# 03_-_28PINS_SCHEMATIC.net
KiCad netlist of a schematic drawn in Altium Designer
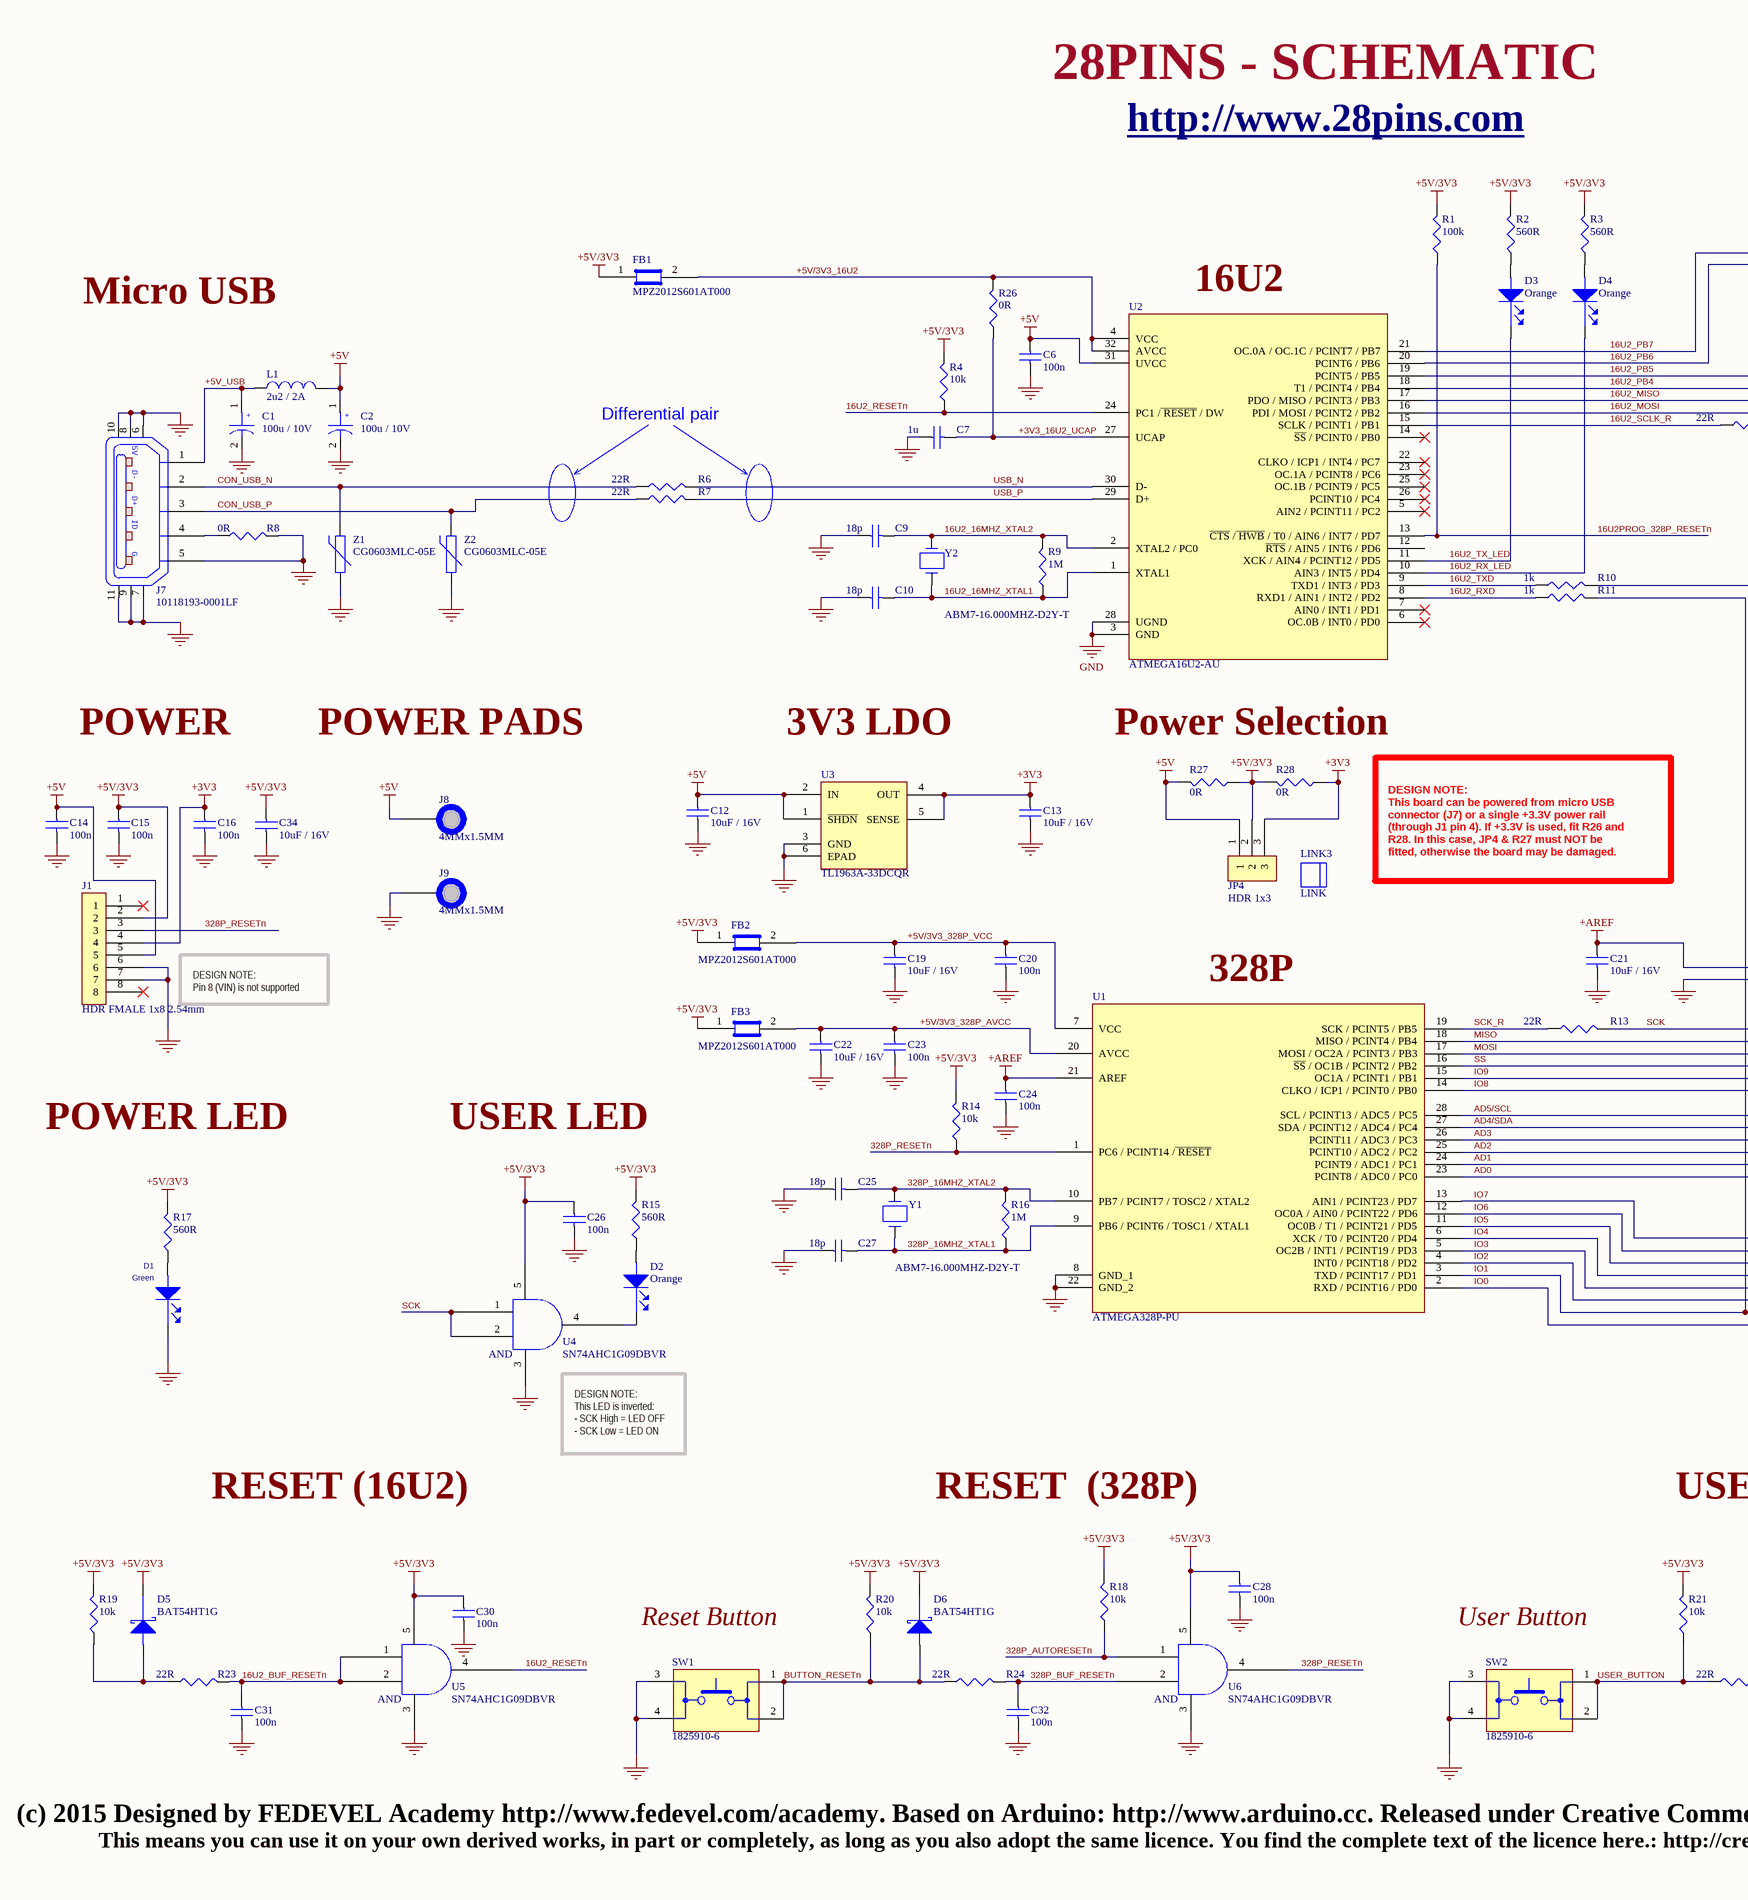
[diagram p0: [03] - 28PINS SCHEMATIC.SchDoc, left]
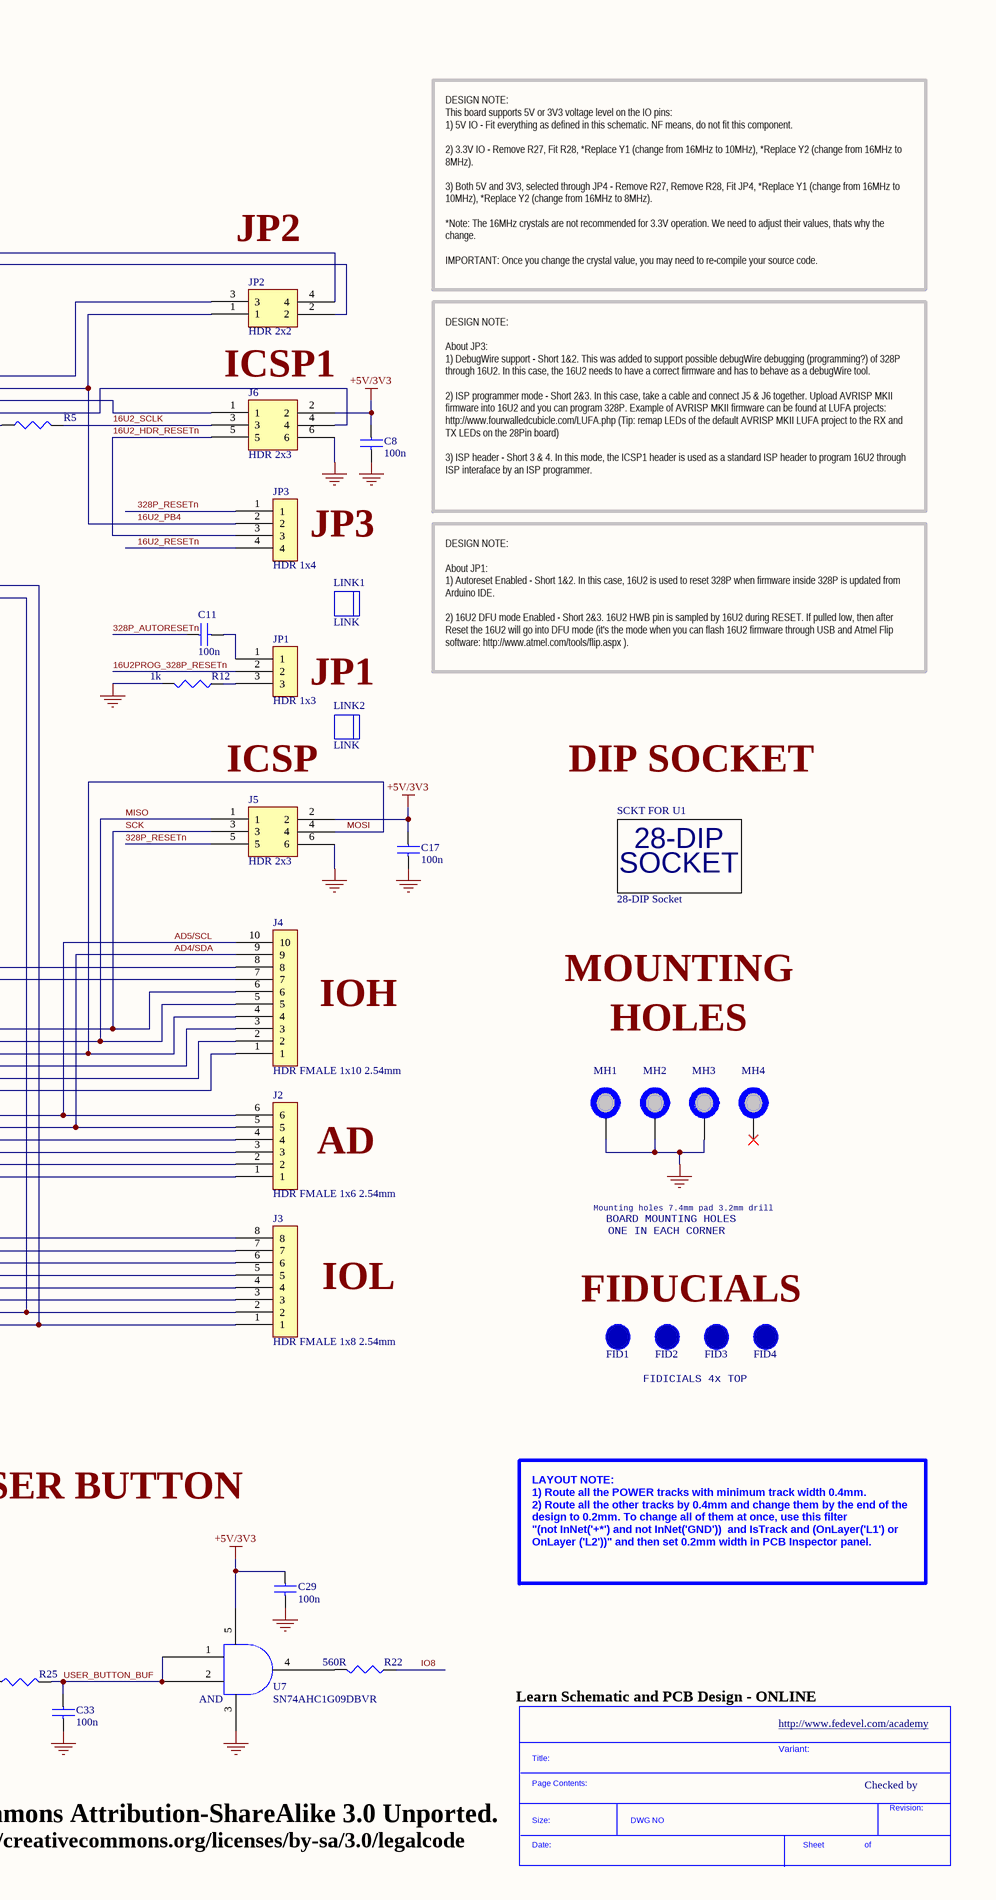
[diagram p1: [03] - 28PINS SCHEMATIC.SchDoc, right]

(export (version "E")
  (design (tool "Eeschema 10.0.6"))
  (components
    (comp (ref "*") (value "SDTitleBlock") (libsource (lib "*") (part "SDTitleBlock")))
    (comp (ref "C1")
      (value "100u / 10V")
      (footprint "C_ALU_C_SIZE")
      (description "CAP ALUM 100UF 10V 20% SMD")
      (fields
        (field (name "MANUFACTURER") "Panasonic Electronic Components")
        (field (name "MANUFACTURER PART NUMBER") "EEE-1AA101WR")
        (field (name ".CREATOR") "MM")
        (field (name ".CHECKED PCB") "RF")
        (field (name ".CHECKED SCH") "RF")
      )
      (libsource (lib "Integrated_Library_FEDEVEL_APR_2015") (part "EEE-1AA101WR"))
    )
    (comp (ref "C2")
      (value "100u / 10V")
      (footprint "C_ALU_C_SIZE")
      (description "CAP ALUM 100UF 10V 20% SMD")
      (fields
        (field (name "MANUFACTURER") "Panasonic Electronic Components")
        (field (name "MANUFACTURER PART NUMBER") "EEE-1AA101WR")
        (field (name ".CREATOR") "MM")
        (field (name ".CHECKED PCB") "RF")
        (field (name ".CHECKED SCH") "RF")
      )
      (libsource (lib "Integrated_Library_FEDEVEL_APR_2015") (part "EEE-1AA101WR"))
    )
    (comp (ref "C6")
      (value "100n")
      (footprint "C0805")
      (description "CAP CER 0.1UF 50V 10% X7R 0805")
      (fields
        (field (name "MANUFACTURER") "TDK Corporation")
        (field (name "MANUFACTURER PART NUMBER") "C2012X7R1H104K085AA")
        (field (name ".CREATOR") "MM")
        (field (name ".CHECKED PCB") "RF")
        (field (name ".CHECKED SCH") "RF")
      )
      (libsource (lib "Integrated_Library_FEDEVEL_APR_2015") (part "C2012X7R1H104K085AA"))
    )
    (comp (ref "C7")
      (value "1u")
      (footprint "C0805")
      (description "CAP CER 1UF 25V 10% X5R 0805")
      (fields
        (field (name "MANUFACTURER") "TDK Corporation")
        (field (name "MANUFACTURER PART NUMBER") "C2012X5R1E105K125AA")
        (field (name ".CREATOR") "MM")
        (field (name ".CHECKED PCB") "RF")
        (field (name ".CHECKED SCH") "RF")
      )
      (libsource (lib "Integrated_Library_FEDEVEL_APR_2015") (part "C2012X5R1E105K125AA"))
    )
    (comp (ref "C8")
      (value "100n")
      (footprint "C0805")
      (description "CAP CER 0.1UF 50V 10% X7R 0805")
      (fields
        (field (name "MANUFACTURER") "TDK Corporation")
        (field (name "MANUFACTURER PART NUMBER") "C2012X7R1H104K085AA")
        (field (name ".CREATOR") "MM")
        (field (name ".CHECKED PCB") "RF")
        (field (name ".CHECKED SCH") "RF")
      )
      (libsource (lib "Integrated_Library_FEDEVEL_APR_2015") (part "C2012X7R1H104K085AA"))
    )
    (comp (ref "C9")
      (value "18p")
      (footprint "C0805")
      (description "CAP CER 18PF 50V 5% NP0 0805")
      (fields
        (field (name "MANUFACTURER") "Kemet")
        (field (name "MANUFACTURER PART NUMBER") "C0805C180J5GACTU")
        (field (name ".CREATOR") "MM")
        (field (name ".CHECKED PCB") "RF")
        (field (name ".CHECKED SCH") "RF")
      )
      (libsource (lib "Integrated_Library_FEDEVEL_APR_2015") (part "C0805C180J5GACTU"))
    )
    (comp (ref "C10")
      (value "18p")
      (footprint "C0805")
      (description "CAP CER 18PF 50V 5% NP0 0805")
      (fields
        (field (name "MANUFACTURER") "Kemet")
        (field (name "MANUFACTURER PART NUMBER") "C0805C180J5GACTU")
        (field (name ".CREATOR") "MM")
        (field (name ".CHECKED PCB") "RF")
        (field (name ".CHECKED SCH") "RF")
      )
      (libsource (lib "Integrated_Library_FEDEVEL_APR_2015") (part "C0805C180J5GACTU"))
    )
    (comp (ref "C11")
      (value "100n")
      (footprint "C0805")
      (description "CAP CER 0.1UF 50V 10% X7R 0805")
      (fields
        (field (name "MANUFACTURER") "TDK Corporation")
        (field (name "MANUFACTURER PART NUMBER") "C2012X7R1H104K085AA")
        (field (name ".CREATOR") "MM")
        (field (name ".CHECKED PCB") "RF")
        (field (name ".CHECKED SCH") "RF")
      )
      (libsource (lib "Integrated_Library_FEDEVEL_APR_2015") (part "C2012X7R1H104K085AA"))
    )
    (comp (ref "C12")
      (value "10uF / 16V")
      (footprint "C0805")
      (description "CAP CER 10UF 16V 20% X5R 0805")
      (fields
        (field (name "MANUFACTURER") "TDK Corporation")
        (field (name "MANUFACTURER PART NUMBER") "C2012X5R1C106M/1.25")
      )
      (libsource (lib "Integrated_Library_FEDEVEL_APR_2015") (part "C2012X5R1C106M"))
    )
    (comp (ref "C13")
      (value "10uF / 16V")
      (footprint "C0805")
      (description "CAP CER 10UF 16V 20% X5R 0805")
      (fields
        (field (name "MANUFACTURER") "TDK Corporation")
        (field (name "MANUFACTURER PART NUMBER") "C2012X5R1C106M/1.25")
      )
      (libsource (lib "Integrated_Library_FEDEVEL_APR_2015") (part "C2012X5R1C106M"))
    )
    (comp (ref "C14")
      (value "100n")
      (footprint "C0805")
      (description "CAP CER 0.1UF 50V 10% X7R 0805")
      (fields
        (field (name "MANUFACTURER") "TDK Corporation")
        (field (name "MANUFACTURER PART NUMBER") "C2012X7R1H104K085AA")
        (field (name ".CREATOR") "MM")
        (field (name ".CHECKED PCB") "RF")
        (field (name ".CHECKED SCH") "RF")
      )
      (libsource (lib "Integrated_Library_FEDEVEL_APR_2015") (part "C2012X7R1H104K085AA"))
    )
    (comp (ref "C15")
      (value "100n")
      (footprint "C0805")
      (description "CAP CER 0.1UF 50V 10% X7R 0805")
      (fields
        (field (name "MANUFACTURER") "TDK Corporation")
        (field (name "MANUFACTURER PART NUMBER") "C2012X7R1H104K085AA")
        (field (name ".CREATOR") "MM")
        (field (name ".CHECKED PCB") "RF")
        (field (name ".CHECKED SCH") "RF")
      )
      (libsource (lib "Integrated_Library_FEDEVEL_APR_2015") (part "C2012X7R1H104K085AA"))
    )
    (comp (ref "C16")
      (value "100n")
      (footprint "C0805")
      (description "CAP CER 0.1UF 50V 10% X7R 0805")
      (fields
        (field (name "MANUFACTURER") "TDK Corporation")
        (field (name "MANUFACTURER PART NUMBER") "C2012X7R1H104K085AA")
        (field (name ".CREATOR") "MM")
        (field (name ".CHECKED PCB") "RF")
        (field (name ".CHECKED SCH") "RF")
      )
      (libsource (lib "Integrated_Library_FEDEVEL_APR_2015") (part "C2012X7R1H104K085AA"))
    )
    (comp (ref "C17")
      (value "100n")
      (footprint "C0805")
      (description "CAP CER 0.1UF 50V 10% X7R 0805")
      (fields
        (field (name "MANUFACTURER") "TDK Corporation")
        (field (name "MANUFACTURER PART NUMBER") "C2012X7R1H104K085AA")
        (field (name ".CREATOR") "MM")
        (field (name ".CHECKED PCB") "RF")
        (field (name ".CHECKED SCH") "RF")
      )
      (libsource (lib "Integrated_Library_FEDEVEL_APR_2015") (part "C2012X7R1H104K085AA"))
    )
    (comp (ref "C19")
      (value "10uF / 16V")
      (footprint "C0805")
      (description "CAP CER 10UF 16V 20% X5R 0805")
      (fields
        (field (name "MANUFACTURER") "TDK Corporation")
        (field (name "MANUFACTURER PART NUMBER") "C2012X5R1C106M/1.25")
      )
      (libsource (lib "Integrated_Library_FEDEVEL_APR_2015") (part "C2012X5R1C106M"))
    )
    (comp (ref "C20")
      (value "100n")
      (footprint "C0805")
      (description "CAP CER 0.1UF 50V 10% X7R 0805")
      (fields
        (field (name "MANUFACTURER") "TDK Corporation")
        (field (name "MANUFACTURER PART NUMBER") "C2012X7R1H104K085AA")
        (field (name ".CREATOR") "MM")
        (field (name ".CHECKED PCB") "RF")
        (field (name ".CHECKED SCH") "RF")
      )
      (libsource (lib "Integrated_Library_FEDEVEL_APR_2015") (part "C2012X7R1H104K085AA"))
    )
    (comp (ref "C21")
      (value "10uF / 16V")
      (footprint "C0805")
      (description "CAP CER 10UF 16V 20% X5R 0805")
      (fields
        (field (name "MANUFACTURER") "TDK Corporation")
        (field (name "MANUFACTURER PART NUMBER") "C2012X5R1C106M/1.25")
      )
      (libsource (lib "Integrated_Library_FEDEVEL_APR_2015") (part "C2012X5R1C106M"))
    )
    (comp (ref "C22")
      (value "10uF / 16V")
      (footprint "C0805")
      (description "CAP CER 10UF 16V 20% X5R 0805")
      (fields
        (field (name "MANUFACTURER") "TDK Corporation")
        (field (name "MANUFACTURER PART NUMBER") "C2012X5R1C106M/1.25")
      )
      (libsource (lib "Integrated_Library_FEDEVEL_APR_2015") (part "C2012X5R1C106M"))
    )
    (comp (ref "C23")
      (value "100n")
      (footprint "C0805")
      (description "CAP CER 0.1UF 50V 10% X7R 0805")
      (fields
        (field (name "MANUFACTURER") "TDK Corporation")
        (field (name "MANUFACTURER PART NUMBER") "C2012X7R1H104K085AA")
        (field (name ".CREATOR") "MM")
        (field (name ".CHECKED PCB") "RF")
        (field (name ".CHECKED SCH") "RF")
      )
      (libsource (lib "Integrated_Library_FEDEVEL_APR_2015") (part "C2012X7R1H104K085AA"))
    )
    (comp (ref "C24")
      (value "100n")
      (footprint "C0805")
      (description "CAP CER 0.1UF 50V 10% X7R 0805")
      (fields
        (field (name "MANUFACTURER") "TDK Corporation")
        (field (name "MANUFACTURER PART NUMBER") "C2012X7R1H104K085AA")
        (field (name ".CREATOR") "MM")
        (field (name ".CHECKED PCB") "RF")
        (field (name ".CHECKED SCH") "RF")
      )
      (libsource (lib "Integrated_Library_FEDEVEL_APR_2015") (part "C2012X7R1H104K085AA"))
    )
    (comp (ref "C25")
      (value "18p")
      (footprint "C0805")
      (description "CAP CER 18PF 50V 5% NP0 0805")
      (fields
        (field (name "MANUFACTURER") "Kemet")
        (field (name "MANUFACTURER PART NUMBER") "C0805C180J5GACTU")
        (field (name ".CREATOR") "MM")
        (field (name ".CHECKED PCB") "RF")
        (field (name ".CHECKED SCH") "RF")
      )
      (libsource (lib "Integrated_Library_FEDEVEL_APR_2015") (part "C0805C180J5GACTU"))
    )
    (comp (ref "C26")
      (value "100n")
      (footprint "C0805")
      (description "CAP CER 0.1UF 50V 10% X7R 0805")
      (fields
        (field (name "MANUFACTURER") "TDK Corporation")
        (field (name "MANUFACTURER PART NUMBER") "C2012X7R1H104K085AA")
        (field (name ".CREATOR") "MM")
        (field (name ".CHECKED PCB") "RF")
        (field (name ".CHECKED SCH") "RF")
      )
      (libsource (lib "Integrated_Library_FEDEVEL_APR_2015") (part "C2012X7R1H104K085AA"))
    )
    (comp (ref "C27")
      (value "18p")
      (footprint "C0805")
      (description "CAP CER 18PF 50V 5% NP0 0805")
      (fields
        (field (name "MANUFACTURER") "Kemet")
        (field (name "MANUFACTURER PART NUMBER") "C0805C180J5GACTU")
        (field (name ".CREATOR") "MM")
        (field (name ".CHECKED PCB") "RF")
        (field (name ".CHECKED SCH") "RF")
      )
      (libsource (lib "Integrated_Library_FEDEVEL_APR_2015") (part "C0805C180J5GACTU"))
    )
    (comp (ref "C28")
      (value "100n")
      (footprint "C0805")
      (description "CAP CER 0.1UF 50V 10% X7R 0805")
      (fields
        (field (name "MANUFACTURER") "TDK Corporation")
        (field (name "MANUFACTURER PART NUMBER") "C2012X7R1H104K085AA")
        (field (name ".CREATOR") "MM")
        (field (name ".CHECKED PCB") "RF")
        (field (name ".CHECKED SCH") "RF")
      )
      (libsource (lib "Integrated_Library_FEDEVEL_APR_2015") (part "C2012X7R1H104K085AA"))
    )
    (comp (ref "C29")
      (value "100n")
      (footprint "C0805")
      (description "CAP CER 0.1UF 50V 10% X7R 0805")
      (fields
        (field (name "MANUFACTURER") "TDK Corporation")
        (field (name "MANUFACTURER PART NUMBER") "C2012X7R1H104K085AA")
        (field (name ".CREATOR") "MM")
        (field (name ".CHECKED PCB") "RF")
        (field (name ".CHECKED SCH") "RF")
      )
      (libsource (lib "Integrated_Library_FEDEVEL_APR_2015") (part "C2012X7R1H104K085AA"))
    )
    (comp (ref "C30")
      (value "100n")
      (footprint "C0805")
      (description "CAP CER 0.1UF 50V 10% X7R 0805")
      (fields
        (field (name "MANUFACTURER") "TDK Corporation")
        (field (name "MANUFACTURER PART NUMBER") "C2012X7R1H104K085AA")
        (field (name ".CREATOR") "MM")
        (field (name ".CHECKED PCB") "RF")
        (field (name ".CHECKED SCH") "RF")
      )
      (libsource (lib "Integrated_Library_FEDEVEL_APR_2015") (part "C2012X7R1H104K085AA"))
    )
    (comp (ref "C31")
      (value "100n")
      (footprint "C0805")
      (description "CAP CER 0.1UF 50V 10% X7R 0805")
      (fields
        (field (name "MANUFACTURER") "TDK Corporation")
        (field (name "MANUFACTURER PART NUMBER") "C2012X7R1H104K085AA")
        (field (name ".CREATOR") "MM")
        (field (name ".CHECKED PCB") "RF")
        (field (name ".CHECKED SCH") "RF")
      )
      (libsource (lib "Integrated_Library_FEDEVEL_APR_2015") (part "C2012X7R1H104K085AA"))
    )
    (comp (ref "C32")
      (value "100n")
      (footprint "C0805")
      (description "CAP CER 0.1UF 50V 10% X7R 0805")
      (fields
        (field (name "MANUFACTURER") "TDK Corporation")
        (field (name "MANUFACTURER PART NUMBER") "C2012X7R1H104K085AA")
        (field (name ".CREATOR") "MM")
        (field (name ".CHECKED PCB") "RF")
        (field (name ".CHECKED SCH") "RF")
      )
      (libsource (lib "Integrated_Library_FEDEVEL_APR_2015") (part "C2012X7R1H104K085AA"))
    )
    (comp (ref "C33")
      (value "100n")
      (footprint "C0805")
      (description "CAP CER 0.1UF 50V 10% X7R 0805")
      (fields
        (field (name "MANUFACTURER") "TDK Corporation")
        (field (name "MANUFACTURER PART NUMBER") "C2012X7R1H104K085AA")
        (field (name ".CREATOR") "MM")
        (field (name ".CHECKED PCB") "RF")
        (field (name ".CHECKED SCH") "RF")
      )
      (libsource (lib "Integrated_Library_FEDEVEL_APR_2015") (part "C2012X7R1H104K085AA"))
    )
    (comp (ref "C34")
      (value "10uF / 16V")
      (footprint "C0805")
      (description "CAP CER 10UF 16V 20% X5R 0805")
      (fields
        (field (name "MANUFACTURER") "TDK Corporation")
        (field (name "MANUFACTURER PART NUMBER") "C2012X5R1C106M/1.25")
      )
      (libsource (lib "Integrated_Library_FEDEVEL_APR_2015") (part "C2012X5R1C106M"))
    )
    (comp (ref "D1")
      (value "Green")
      (footprint "LED_0603")
      (description "LED SMARTLED GREEN 570NM 0603")
      (fields
        (field (name "MANUFACTURER") "OSRAM Opto Semiconductors Inc")
        (field (name "MANUFACTURER PART NUMBER") "LG L29K-G2J1-24-Z")
      )
      (libsource (lib "Integrated_Library_FEDEVEL_APR_2015") (part "LG L29K-G2J1-24-Z"))
    )
    (comp (ref "D2")
      (value "Orange")
      (footprint "LED_0603")
      (description "LED SMARTLED ORANGE 606NM 0603")
      (fields
        (field (name "MANUFACTURER") "OSRAM Opto Semiconductors Inc")
        (field (name "MANUFACTURER PART NUMBER") "LO L29K-H2K1-24-Z")
      )
      (libsource (lib "Integrated_Library_FEDEVEL_APR_2015") (part "LO L29K-H2K1-24-Z"))
    )
    (comp (ref "D3")
      (value "Orange")
      (footprint "LED_0603")
      (description "LED SMARTLED ORANGE 606NM 0603")
      (fields
        (field (name "MANUFACTURER") "OSRAM Opto Semiconductors Inc")
        (field (name "MANUFACTURER PART NUMBER") "LO L29K-H2K1-24-Z")
      )
      (libsource (lib "Integrated_Library_FEDEVEL_APR_2015") (part "LO L29K-H2K1-24-Z"))
    )
    (comp (ref "D4")
      (value "Orange")
      (footprint "LED_0603")
      (description "LED SMARTLED ORANGE 606NM 0603")
      (fields
        (field (name "MANUFACTURER") "OSRAM Opto Semiconductors Inc")
        (field (name "MANUFACTURER PART NUMBER") "LO L29K-H2K1-24-Z")
      )
      (libsource (lib "Integrated_Library_FEDEVEL_APR_2015") (part "LO L29K-H2K1-24-Z"))
    )
    (comp (ref "D5")
      (value "BAT54HT1G")
      (footprint "SOD323")
      (description "DIODE SCHOTTKY 30V 0.2A SOD323")
      (fields (field (name "MANUFACTURER") "Fairchild Semiconductor") (field (name ".CREATOR") "MM"))
      (libsource (lib "Integrated_Library_FEDEVEL_APR_2015") (part "BAT54HT1G"))
    )
    (comp (ref "D6")
      (value "BAT54HT1G")
      (footprint "SOD323")
      (description "DIODE SCHOTTKY 30V 0.2A SOD323")
      (fields (field (name "MANUFACTURER") "Fairchild Semiconductor") (field (name ".CREATOR") "MM"))
      (libsource (lib "Integrated_Library_FEDEVEL_APR_2015") (part "BAT54HT1G"))
    )
    (comp (ref "FB1")
      (value "MPZ2012S601AT000")
      (footprint "C0805")
      (description "FERRITE CHIP BEAD 600 OHM SMD")
      (fields
        (field (name "MANUFACTURER") "TDK Corporation")
        (field (name ".CREATOR") "MM")
        (field (name ".CHECKED PCB") "RF")
        (field (name ".CHECKED SCH") "RF")
      )
      (libsource (lib "Integrated_Library_FEDEVEL_APR_2015") (part "MPZ2012S601AT000"))
    )
    (comp (ref "FB2")
      (value "MPZ2012S601AT000")
      (footprint "C0805")
      (description "FERRITE CHIP BEAD 600 OHM SMD")
      (fields
        (field (name "MANUFACTURER") "TDK Corporation")
        (field (name ".CREATOR") "MM")
        (field (name ".CHECKED PCB") "RF")
        (field (name ".CHECKED SCH") "RF")
      )
      (libsource (lib "Integrated_Library_FEDEVEL_APR_2015") (part "MPZ2012S601AT000"))
    )
    (comp (ref "FB3")
      (value "MPZ2012S601AT000")
      (footprint "C0805")
      (description "FERRITE CHIP BEAD 600 OHM SMD")
      (fields
        (field (name "MANUFACTURER") "TDK Corporation")
        (field (name ".CREATOR") "MM")
        (field (name ".CHECKED PCB") "RF")
        (field (name ".CHECKED SCH") "RF")
      )
      (libsource (lib "Integrated_Library_FEDEVEL_APR_2015") (part "MPZ2012S601AT000"))
    )
    (comp (ref "FID1")
      (value "FID_1MMC")
      (footprint "FID_40X120D")
      (description "Fiducial 40mil Diameter, 120mil Mask")
      (libsource (lib "Integrated_Library_FEDEVEL_APR_2015") (part "FID_1MMC"))
    )
    (comp (ref "FID2")
      (value "FID_1MMC")
      (footprint "FID_40X120D")
      (description "Fiducial 40mil Diameter, 120mil Mask")
      (libsource (lib "Integrated_Library_FEDEVEL_APR_2015") (part "FID_1MMC"))
    )
    (comp (ref "FID3")
      (value "FID_1MMC")
      (footprint "FID_40X120D")
      (description "Fiducial 40mil Diameter, 120mil Mask")
      (libsource (lib "Integrated_Library_FEDEVEL_APR_2015") (part "FID_1MMC"))
    )
    (comp (ref "FID4")
      (value "FID_1MMC")
      (footprint "FID_40X120D")
      (description "Fiducial 40mil Diameter, 120mil Mask")
      (libsource (lib "Integrated_Library_FEDEVEL_APR_2015") (part "FID_1MMC"))
    )
    (comp (ref "J1")
      (value "HDR FMALE 1x8 2.54mm")
      (footprint "Hdr_Female_1x8_2.54mm")
      (description "08-WAY SIL VERT SOCKET L/FREE")
      (fields
        (field (name "MANUFACTURER") "Harwin Inc")
        (field (name "MANUFACTURER PART NUMBER") "M20-7820842")
        (field (name ".CREATOR") "MM")
        (field (name ".CHECKED PCB") "RF")
        (field (name ".CHECKED SCH") "RF")
      )
      (libsource (lib "") (part "M20-7820842_1"))
    )
    (comp (ref "J2")
      (value "HDR FMALE 1x6 2.54mm")
      (footprint "Hdr_Female_1x6_2.54mm")
      (description "06-WAY SIL VERT SOCKET L/FREE")
      (fields
        (field (name "MANUFACTURER") "Harwin Inc")
        (field (name "MANUFACTURER PART NUMBER") "M20-7820646")
        (field (name ".CHECKED PCB") "MM")
        (field (name ".CHECKED SCH") "MM")
        (field (name ".CREATOR") "MM")
      )
      (libsource (lib "Integrated_Library_FEDEVEL_APR_2015") (part "M20-7820646"))
    )
    (comp (ref "J3")
      (value "HDR FMALE 1x8 2.54mm")
      (footprint "Hdr_Female_1x8_2.54mm")
      (description "08-WAY SIL VERT SOCKET L/FREE")
      (fields
        (field (name "MANUFACTURER") "Harwin Inc")
        (field (name "MANUFACTURER PART NUMBER") "M20-7820842")
        (field (name ".CREATOR") "MM")
        (field (name ".CHECKED PCB") "RF")
        (field (name ".CHECKED SCH") "RF")
      )
      (libsource (lib "Integrated_Library_FEDEVEL_APR_2015") (part "M20-7820842"))
    )
    (comp (ref "J4")
      (value "HDR FMALE 1x10 2.54mm")
      (footprint "Hdr_Female_1x10_2.54mm")
      (description "10-WAY SIL VERT SOCKET L/FREE")
      (fields
        (field (name "MANUFACTURER") "Harwin Inc")
        (field (name "MANUFACTURER PART NUMBER") "M20-7821046")
        (field (name ".CREATOR") "MM")
        (field (name ".CHECKED PCB") "RF")
        (field (name ".CHECKED SCH") "RF")
      )
      (libsource (lib "Integrated_Library_FEDEVEL_APR_2015") (part "M20-7821046"))
    )
    (comp (ref "J5")
      (value "HDR 2x3")
      (footprint "HDR_2x3_2.54MM")
      (description "CONN HEADER 6POS .100 STR 30AU")
      (fields
        (field (name "MANUFACTURER") "FCI")
        (field (name "MANUFACTURER PART NUMBER") "67997-106HLF")
        (field (name ".CREATOR") "MM")
        (field (name ".CHECKED PCB") "RF")
        (field (name ".CHECKED SCH") "RF")
      )
      (libsource (lib "Integrated_Library_FEDEVEL_APR_2015") (part "67997-106HLF"))
    )
    (comp (ref "J6")
      (value "HDR 2x3")
      (footprint "HDR_2x3_2.54MM")
      (description "CONN HEADER 6POS .100 STR 30AU")
      (fields
        (field (name "MANUFACTURER") "FCI")
        (field (name "MANUFACTURER PART NUMBER") "67997-106HLF")
        (field (name ".CREATOR") "MM")
        (field (name ".CHECKED PCB") "RF")
        (field (name ".CHECKED SCH") "RF")
      )
      (libsource (lib "Integrated_Library_FEDEVEL_APR_2015") (part "67997-106HLF"))
    )
    (comp (ref "J7")
      (value "10118193-0001LF")
      (footprint "10118193")
      (description "CONN USB MICRO B RECPT SMT R/A")
      (fields
        (field (name "MANUFACTURER") "FCI")
        (field (name ".CREATOR") "MM")
        (field (name ".CHECKED PCB") "RF")
        (field (name ".CHECKED SCH") "MM")
      )
      (libsource (lib "Integrated_Library_FEDEVEL_APR_2015") (part "10118193-0001LF"))
    )
    (comp (ref "J8")
      (value "4MMx1.5MM")
      (footprint "PAD_WITH_HOLE_4MMx1.5MM")
      (description "Pad with a hole 4mm x 1.5mm")
      (libsource (lib "Integrated_Library_FEDEVEL_APR_2015") (part "PAD_WITH_HOLE_4MMx1.5MM"))
    )
    (comp (ref "J9")
      (value "4MMx1.5MM")
      (footprint "PAD_WITH_HOLE_4MMx1.5MM")
      (description "Pad with a hole 4mm x 1.5mm")
      (libsource (lib "Integrated_Library_FEDEVEL_APR_2015") (part "PAD_WITH_HOLE_4MMx1.5MM"))
    )
    (comp (ref "JP1")
      (value "HDR 1x3")
      (footprint "Hdr_1x3_2.54mm")
      (description "BERGSTIK II .100\" SR STRAIGHT")
      (fields
        (field (name "MANUFACTURER") "FCI")
        (field (name "MANUFACTURER PART NUMBER") "68000-103HLF")
        (field (name ".CREATOR") "MM")
      )
      (libsource (lib "Integrated_Library_FEDEVEL_APR_2015") (part "68000-103HLF"))
    )
    (comp (ref "JP2")
      (value "HDR 2x2")
      (footprint "HDR_2x2_2.54MM")
      (description "CONN HEADER 4POS .100 STR 15AU")
      (fields
        (field (name "MANUFACTURER") "FCI")
        (field (name "MANUFACTURER PART NUMBER") "68602-204HLF")
        (field (name ".CREATOR") "MM")
        (field (name ".CHECKED PCB") "RF")
        (field (name ".CHECKED SCH") "RF")
      )
      (libsource (lib "Integrated_Library_FEDEVEL_APR_2015") (part "68602-204HLF"))
    )
    (comp (ref "JP3")
      (value "HDR 1x4")
      (footprint "HDR_1x4_2.54MM")
      (description "CONN HEADER 4POS .100 STR 15AU")
      (fields
        (field (name "MANUFACTURER") "FCI")
        (field (name "MANUFACTURER PART NUMBER") "68001-204HLF")
        (field (name ".CHECKED PCB") "RF")
        (field (name ".CHECKED SCH") "RF")
      )
      (libsource (lib "Integrated_Library_FEDEVEL_APR_2015") (part "68001-204HLF"))
    )
    (comp (ref "JP4")
      (value "HDR 1x3")
      (footprint "Hdr_1x3_2.54mm")
      (description "BERGSTIK II .100\" SR STRAIGHT")
      (fields
        (field (name "MANUFACTURER") "FCI")
        (field (name "MANUFACTURER PART NUMBER") "68000-103HLF")
        (field (name ".CREATOR") "MM")
      )
      (libsource (lib "") (part "68000-103HLF_1"))
    )
    (comp (ref "L1")
      (value "2u2 / 2A")
      (footprint "C1210_IND")
      (description "FIXED IND 2.2UH 2A 80 MOHM SMD")
      (fields
        (field (name "MANUFACTURER") "Kemet")
        (field (name "MANUFACTURER PART NUMBER") "L1210R2R2MDWIT")
        (field (name ".CREATOR") "MM")
        (field (name ".CHECKED PCB") "RF")
        (field (name ".CHECKED SCH") "RF")
      )
      (libsource (lib "Integrated_Library_FEDEVEL_APR_2015") (part "L1210R2R2MDWIT"))
    )
    (comp (ref "LINK1")
      (value "LINK")
      (description "CONN JUMPER SHORTING .100\" GOLD")
      (fields
        (field (name "MANUFACTURER") "Sullins Connector Solutions")
        (field (name "MANUFACTURER PART NUMBER") "QPC02SXGN-RC")
      )
      (libsource (lib "Integrated_Library_FEDEVEL_APR_2015") (part "QPC02SXGN-RC"))
    )
    (comp (ref "LINK2")
      (value "LINK")
      (description "CONN JUMPER SHORTING .100\" GOLD")
      (fields
        (field (name "MANUFACTURER") "Sullins Connector Solutions")
        (field (name "MANUFACTURER PART NUMBER") "QPC02SXGN-RC")
      )
      (libsource (lib "Integrated_Library_FEDEVEL_APR_2015") (part "QPC02SXGN-RC"))
    )
    (comp (ref "LINK3")
      (value "LINK")
      (description "CONN JUMPER SHORTING .100\" GOLD")
      (fields
        (field (name "MANUFACTURER") "Sullins Connector Solutions")
        (field (name "MANUFACTURER PART NUMBER") "QPC02SXGN-RC")
      )
      (libsource (lib "Integrated_Library_FEDEVEL_APR_2015") (part "QPC02SXGN-RC"))
    )
    (comp (ref "MH1")
      (value "MH_7.4MMC_3.2MMD")
      (footprint "MH_7.4MMD_3.2MMD")
      (description "Mounting Hole 7.4mm Diameter, 3.2mm Drill")
      (fields (field (name ".CREATOR") "MM"))
      (libsource (lib "Integrated_Library_FEDEVEL_APR_2015") (part "MH_7.4MMC_3.2MMD"))
    )
    (comp (ref "MH2")
      (value "MH_7.4MMC_3.2MMD")
      (footprint "MH_7.4MMD_3.2MMD")
      (description "Mounting Hole 7.4mm Diameter, 3.2mm Drill")
      (fields (field (name ".CREATOR") "MM"))
      (libsource (lib "Integrated_Library_FEDEVEL_APR_2015") (part "MH_7.4MMC_3.2MMD"))
    )
    (comp (ref "MH3")
      (value "MH_7.4MMC_3.2MMD")
      (footprint "MH_7.4MMD_3.2MMD")
      (description "Mounting Hole 7.4mm Diameter, 3.2mm Drill")
      (fields (field (name ".CREATOR") "MM"))
      (libsource (lib "Integrated_Library_FEDEVEL_APR_2015") (part "MH_7.4MMC_3.2MMD"))
    )
    (comp (ref "MH4")
      (value "MH_7.4MMNC_3.2MMD")
      (footprint "MH_7.4MMD_3.2MMD_NON_COPPER_NPTH")
      (description "Mounting Hole 7.4mm Diameter (Non Copper), 3.2mm Drill NPTH")
      (libsource (lib "Integrated_Library_FEDEVEL_APR_2015") (part "MH_7.4MMNC_3.2MMD"))
    )
    (comp (ref "R1")
      (value "100k")
      (footprint "R0805")
      (description "RES SMD 100K OHM 1% 1/8W 0805")
      (fields
        (field (name "MANUFACTURER") "Yageo")
        (field (name "MANUFACTURER PART NUMBER") "RC0805FR-07100KL")
        (field (name ".CREATOR") "MM")
        (field (name ".CHECKED PCB") "RF")
        (field (name ".CHECKED SCH") "RF")
      )
      (libsource (lib "Integrated_Library_FEDEVEL_APR_2015") (part "RC0805FR-07100KL"))
    )
    (comp (ref "R2")
      (value "560R")
      (footprint "R0805")
      (description "RES SMD 560 OHM 1% 1/8W 0805")
      (fields
        (field (name "MANUFACTURER") "Yageo")
        (field (name "MANUFACTURER PART NUMBER") "RC0805FR-07560RL")
        (field (name ".CREATOR") "MM")
        (field (name ".CHECKED PCB") "RF")
        (field (name ".CHECKED SCH") "RF")
      )
      (libsource (lib "Integrated_Library_FEDEVEL_APR_2015") (part "RC0805FR-07560RL"))
    )
    (comp (ref "R3")
      (value "560R")
      (footprint "R0805")
      (description "RES SMD 560 OHM 1% 1/8W 0805")
      (fields
        (field (name "MANUFACTURER") "Yageo")
        (field (name "MANUFACTURER PART NUMBER") "RC0805FR-07560RL")
        (field (name ".CREATOR") "MM")
        (field (name ".CHECKED PCB") "RF")
        (field (name ".CHECKED SCH") "RF")
      )
      (libsource (lib "Integrated_Library_FEDEVEL_APR_2015") (part "RC0805FR-07560RL"))
    )
    (comp (ref "R4")
      (value "10k")
      (footprint "R0805")
      (description "RES SMD 10K OHM 1% 1/8W 0805")
      (fields
        (field (name "MANUFACTURER") "Yageo")
        (field (name "MANUFACTURER PART NUMBER") "RC0805FR-0710KL")
        (field (name ".CREATOR") "MM")
        (field (name ".CHECKED PCB") "RF")
        (field (name ".CHECKED SCH") "RF")
      )
      (libsource (lib "Integrated_Library_FEDEVEL_APR_2015") (part "RC0805FR-0710KL"))
    )
    (comp (ref "R5")
      (value "22R")
      (footprint "R0805")
      (description "RES SMD 22 OHM 1% 1/8W 0805")
      (fields
        (field (name "MANUFACTURER") "Yageo")
        (field (name "MANUFACTURER PART NUMBER") "RC0805FR-0722RL")
        (field (name ".CREATOR") "MM")
        (field (name ".CHECKED PCB") "RF")
        (field (name ".CHECKED SCH") "RF")
      )
      (libsource (lib "Integrated_Library_FEDEVEL_APR_2015") (part "RC0805FR-0722RL"))
    )
    (comp (ref "R6")
      (value "22R")
      (footprint "R0805")
      (description "RES SMD 22 OHM 1% 1/8W 0805")
      (fields
        (field (name "MANUFACTURER") "Yageo")
        (field (name "MANUFACTURER PART NUMBER") "RC0805FR-0722RL")
        (field (name ".CREATOR") "MM")
        (field (name ".CHECKED PCB") "RF")
        (field (name ".CHECKED SCH") "RF")
      )
      (libsource (lib "Integrated_Library_FEDEVEL_APR_2015") (part "RC0805FR-0722RL"))
    )
    (comp (ref "R7")
      (value "22R")
      (footprint "R0805")
      (description "RES SMD 22 OHM 1% 1/8W 0805")
      (fields
        (field (name "MANUFACTURER") "Yageo")
        (field (name "MANUFACTURER PART NUMBER") "RC0805FR-0722RL")
        (field (name ".CREATOR") "MM")
        (field (name ".CHECKED PCB") "RF")
        (field (name ".CHECKED SCH") "RF")
      )
      (libsource (lib "Integrated_Library_FEDEVEL_APR_2015") (part "RC0805FR-0722RL"))
    )
    (comp (ref "R8")
      (value "0R")
      (footprint "R0805")
      (description "RES 0.0 OHM 1/8W 0805 SMD")
      (fields
        (field (name "MANUFACTURER") "Yageo")
        (field (name "MANUFACTURER PART NUMBER") "RC0805JR-070RL")
        (field (name ".CHECKED PCB") "RF")
        (field (name ".CHECKED SCH") "RF")
      )
      (libsource (lib "Integrated_Library_FEDEVEL_APR_2015") (part "RC0805JR-070RL"))
    )
    (comp (ref "R9")
      (value "1M")
      (footprint "R0805")
      (description "RES SMD 1M OHM 1% 1/8W 0805")
      (fields
        (field (name "MANUFACTURER") "Yageo")
        (field (name "MANUFACTURER PART NUMBER") "RC0805FR-071ML")
        (field (name ".CREATOR") "MM")
        (field (name ".CHECKED PCB") "RF")
        (field (name ".CHECKED SCH") "RF")
      )
      (libsource (lib "Integrated_Library_FEDEVEL_APR_2015") (part "RC0805FR-071ML"))
    )
    (comp (ref "R10")
      (value "1k")
      (footprint "R0805")
      (description "RES SMD 1K OHM 1% 1/8W 0805")
      (fields
        (field (name "MANUFACTURER") "Yageo")
        (field (name "MANUFACTURER PART NUMBER") "RC0805FR-071KL")
        (field (name ".CREATOR") "MM")
        (field (name ".CHECKED PCB") "RF")
        (field (name ".CHECKED SCH") "RF")
      )
      (libsource (lib "Integrated_Library_FEDEVEL_APR_2015") (part "RC0805FR-071KL"))
    )
    (comp (ref "R11")
      (value "1k")
      (footprint "R0805")
      (description "RES SMD 1K OHM 1% 1/8W 0805")
      (fields
        (field (name "MANUFACTURER") "Yageo")
        (field (name "MANUFACTURER PART NUMBER") "RC0805FR-071KL")
        (field (name ".CREATOR") "MM")
        (field (name ".CHECKED PCB") "RF")
        (field (name ".CHECKED SCH") "RF")
      )
      (libsource (lib "Integrated_Library_FEDEVEL_APR_2015") (part "RC0805FR-071KL"))
    )
    (comp (ref "R12")
      (value "1k")
      (footprint "R0805")
      (description "RES SMD 1K OHM 1% 1/8W 0805")
      (fields
        (field (name "MANUFACTURER") "Yageo")
        (field (name "MANUFACTURER PART NUMBER") "RC0805FR-071KL")
        (field (name ".CREATOR") "MM")
        (field (name ".CHECKED PCB") "RF")
        (field (name ".CHECKED SCH") "RF")
      )
      (libsource (lib "Integrated_Library_FEDEVEL_APR_2015") (part "RC0805FR-071KL"))
    )
    (comp (ref "R13")
      (value "22R")
      (footprint "R0805")
      (description "RES SMD 22 OHM 1% 1/8W 0805")
      (fields
        (field (name "MANUFACTURER") "Yageo")
        (field (name "MANUFACTURER PART NUMBER") "RC0805FR-0722RL")
        (field (name ".CREATOR") "MM")
        (field (name ".CHECKED PCB") "RF")
        (field (name ".CHECKED SCH") "RF")
      )
      (libsource (lib "Integrated_Library_FEDEVEL_APR_2015") (part "RC0805FR-0722RL"))
    )
    (comp (ref "R14")
      (value "10k")
      (footprint "R0805")
      (description "RES SMD 10K OHM 1% 1/8W 0805")
      (fields
        (field (name "MANUFACTURER") "Yageo")
        (field (name "MANUFACTURER PART NUMBER") "RC0805FR-0710KL")
        (field (name ".CREATOR") "MM")
        (field (name ".CHECKED PCB") "RF")
        (field (name ".CHECKED SCH") "RF")
      )
      (libsource (lib "Integrated_Library_FEDEVEL_APR_2015") (part "RC0805FR-0710KL"))
    )
    (comp (ref "R15")
      (value "560R")
      (footprint "R0805")
      (description "RES SMD 560 OHM 1% 1/8W 0805")
      (fields
        (field (name "MANUFACTURER") "Yageo")
        (field (name "MANUFACTURER PART NUMBER") "RC0805FR-07560RL")
        (field (name ".CREATOR") "MM")
        (field (name ".CHECKED PCB") "RF")
        (field (name ".CHECKED SCH") "RF")
      )
      (libsource (lib "Integrated_Library_FEDEVEL_APR_2015") (part "RC0805FR-07560RL"))
    )
    (comp (ref "R16")
      (value "1M")
      (footprint "R0805")
      (description "RES SMD 1M OHM 1% 1/8W 0805")
      (fields
        (field (name "MANUFACTURER") "Yageo")
        (field (name "MANUFACTURER PART NUMBER") "RC0805FR-071ML")
        (field (name ".CREATOR") "MM")
        (field (name ".CHECKED PCB") "RF")
        (field (name ".CHECKED SCH") "RF")
      )
      (libsource (lib "Integrated_Library_FEDEVEL_APR_2015") (part "RC0805FR-071ML"))
    )
    (comp (ref "R17")
      (value "560R")
      (footprint "R0805")
      (description "RES SMD 560 OHM 1% 1/8W 0805")
      (fields
        (field (name "MANUFACTURER") "Yageo")
        (field (name "MANUFACTURER PART NUMBER") "RC0805FR-07560RL")
        (field (name ".CREATOR") "MM")
        (field (name ".CHECKED PCB") "RF")
        (field (name ".CHECKED SCH") "RF")
      )
      (libsource (lib "Integrated_Library_FEDEVEL_APR_2015") (part "RC0805FR-07560RL"))
    )
    (comp (ref "R18")
      (value "10k")
      (footprint "R0805")
      (description "RES SMD 10K OHM 1% 1/8W 0805")
      (fields
        (field (name "MANUFACTURER") "Yageo")
        (field (name "MANUFACTURER PART NUMBER") "RC0805FR-0710KL")
        (field (name ".CREATOR") "MM")
        (field (name ".CHECKED PCB") "RF")
        (field (name ".CHECKED SCH") "RF")
      )
      (libsource (lib "Integrated_Library_FEDEVEL_APR_2015") (part "RC0805FR-0710KL"))
    )
    (comp (ref "R19")
      (value "10k")
      (footprint "R0805")
      (description "RES SMD 10K OHM 1% 1/8W 0805")
      (fields
        (field (name "MANUFACTURER") "Yageo")
        (field (name "MANUFACTURER PART NUMBER") "RC0805FR-0710KL")
        (field (name ".CREATOR") "MM")
        (field (name ".CHECKED PCB") "RF")
        (field (name ".CHECKED SCH") "RF")
      )
      (libsource (lib "Integrated_Library_FEDEVEL_APR_2015") (part "RC0805FR-0710KL"))
    )
    (comp (ref "R20")
      (value "10k")
      (footprint "R0805")
      (description "RES SMD 10K OHM 1% 1/8W 0805")
      (fields
        (field (name "MANUFACTURER") "Yageo")
        (field (name "MANUFACTURER PART NUMBER") "RC0805FR-0710KL")
        (field (name ".CREATOR") "MM")
        (field (name ".CHECKED PCB") "RF")
        (field (name ".CHECKED SCH") "RF")
      )
      (libsource (lib "Integrated_Library_FEDEVEL_APR_2015") (part "RC0805FR-0710KL"))
    )
    (comp (ref "R21")
      (value "10k")
      (footprint "R0805")
      (description "RES SMD 10K OHM 1% 1/8W 0805")
      (fields
        (field (name "MANUFACTURER") "Yageo")
        (field (name "MANUFACTURER PART NUMBER") "RC0805FR-0710KL")
        (field (name ".CREATOR") "MM")
        (field (name ".CHECKED PCB") "RF")
        (field (name ".CHECKED SCH") "RF")
      )
      (libsource (lib "Integrated_Library_FEDEVEL_APR_2015") (part "RC0805FR-0710KL"))
    )
    (comp (ref "R22")
      (value "560R")
      (footprint "R0805")
      (description "RES SMD 560 OHM 1% 1/8W 0805")
      (fields
        (field (name "MANUFACTURER") "Yageo")
        (field (name "MANUFACTURER PART NUMBER") "RC0805FR-07560RL")
        (field (name ".CREATOR") "MM")
        (field (name ".CHECKED PCB") "RF")
        (field (name ".CHECKED SCH") "RF")
      )
      (libsource (lib "Integrated_Library_FEDEVEL_APR_2015") (part "RC0805FR-07560RL"))
    )
    (comp (ref "R23")
      (value "22R")
      (footprint "R0805")
      (description "RES SMD 22 OHM 1% 1/8W 0805")
      (fields
        (field (name "MANUFACTURER") "Yageo")
        (field (name "MANUFACTURER PART NUMBER") "RC0805FR-0722RL")
        (field (name ".CREATOR") "MM")
        (field (name ".CHECKED PCB") "RF")
        (field (name ".CHECKED SCH") "RF")
      )
      (libsource (lib "Integrated_Library_FEDEVEL_APR_2015") (part "RC0805FR-0722RL"))
    )
    (comp (ref "R24")
      (value "22R")
      (footprint "R0805")
      (description "RES SMD 22 OHM 1% 1/8W 0805")
      (fields
        (field (name "MANUFACTURER") "Yageo")
        (field (name "MANUFACTURER PART NUMBER") "RC0805FR-0722RL")
        (field (name ".CREATOR") "MM")
        (field (name ".CHECKED PCB") "RF")
        (field (name ".CHECKED SCH") "RF")
      )
      (libsource (lib "Integrated_Library_FEDEVEL_APR_2015") (part "RC0805FR-0722RL"))
    )
    (comp (ref "R25")
      (value "22R")
      (footprint "R0805")
      (description "RES SMD 22 OHM 1% 1/8W 0805")
      (fields
        (field (name "MANUFACTURER") "Yageo")
        (field (name "MANUFACTURER PART NUMBER") "RC0805FR-0722RL")
        (field (name ".CREATOR") "MM")
        (field (name ".CHECKED PCB") "RF")
        (field (name ".CHECKED SCH") "RF")
      )
      (libsource (lib "Integrated_Library_FEDEVEL_APR_2015") (part "RC0805FR-0722RL"))
    )
    (comp (ref "R26")
      (value "0R")
      (footprint "R0805")
      (description "RES 0.0 OHM 1/8W 0805 SMD")
      (fields
        (field (name "MANUFACTURER") "Yageo")
        (field (name "MANUFACTURER PART NUMBER") "RC0805JR-070RL")
        (field (name ".CHECKED PCB") "RF")
        (field (name ".CHECKED SCH") "RF")
      )
      (libsource (lib "Integrated_Library_FEDEVEL_APR_2015") (part "RC0805JR-070RL"))
    )
    (comp (ref "R27")
      (value "0R")
      (footprint "R0805")
      (description "RES 0.0 OHM 1/8W 0805 SMD")
      (fields
        (field (name "MANUFACTURER") "Yageo")
        (field (name "MANUFACTURER PART NUMBER") "RC0805JR-070RL")
        (field (name ".CHECKED PCB") "RF")
        (field (name ".CHECKED SCH") "RF")
      )
      (libsource (lib "Integrated_Library_FEDEVEL_APR_2015") (part "RC0805JR-070RL"))
    )
    (comp (ref "R28")
      (value "0R")
      (footprint "R0805")
      (description "RES 0.0 OHM 1/8W 0805 SMD")
      (fields
        (field (name "MANUFACTURER") "Yageo")
        (field (name "MANUFACTURER PART NUMBER") "RC0805JR-070RL")
        (field (name ".CHECKED PCB") "RF")
        (field (name ".CHECKED SCH") "RF")
      )
      (libsource (lib "Integrated_Library_FEDEVEL_APR_2015") (part "RC0805JR-070RL"))
    )
    (comp (ref "SCKT FOR U1")
      (value "28-DIP Socket")
      (footprint "28_DIP_7.62mm_SOCKET")
      (description "CONN IC DIP SOCKET 28POS TIN")
      (fields
        (field (name "MANUFACTURER") "3M")
        (field (name "MANUFACTURER PART NUMBER") "4828-3004-CP")
        (field (name ".CREATOR") "MM")
        (field (name ".CHECKED PCB") "RF")
        (field (name ".CHECKED SCH") "RF")
      )
      (libsource (lib "Integrated_Library_FEDEVEL_APR_2015") (part "4828-3004-CP"))
    )
    (comp (ref "SW1")
      (value "1825910-6")
      (footprint "1825910-6")
      (description "SWITCH TACTILE SPST-NO 0.05A 24V")
      (fields
        (field (name "MANUFACTURER") "TE Connectivity")
        (field (name ".CREATOR") "MM")
        (field (name ".CHECKED PCB") "RF")
        (field (name ".CHECKED SCH") "RF")
      )
      (libsource (lib "Integrated_Library_FEDEVEL_APR_2015") (part "1825910-6"))
    )
    (comp (ref "SW2")
      (value "1825910-6")
      (footprint "1825910-6")
      (description "SWITCH TACTILE SPST-NO 0.05A 24V")
      (fields
        (field (name "MANUFACTURER") "TE Connectivity")
        (field (name ".CREATOR") "MM")
        (field (name ".CHECKED PCB") "RF")
        (field (name ".CHECKED SCH") "RF")
      )
      (libsource (lib "Integrated_Library_FEDEVEL_APR_2015") (part "1825910-6"))
    )
    (comp (ref "U1")
      (value "ATMEGA328P-PU")
      (footprint "28_DIP_7.62mm")
      (description "IC MCU 8BIT 32KB FLASH 28DIP")
      (fields
        (field (name "MANUFACTURER") "Atmel")
        (field (name ".CREATOR") "MM")
        (field (name ".CHECKED PCB") "RF")
        (field (name ".CHECKED SCH") "RF")
      )
      (libsource (lib "Integrated_Library_FEDEVEL_APR_2015") (part "ATMEGA328P-PU"))
    )
    (comp (ref "U2")
      (value "ATMEGA16U2-AU")
      (footprint "TQFP32")
      (description "IC MCU 8BIT 16KB FLASH 32TQFP")
      (fields
        (field (name "MANUFACTURER") "Atmel")
        (field (name ".CREATOR") "MM")
        (field (name ".CHECKED PCB") "RF")
        (field (name ".CHECKED SCH") "RF")
      )
      (libsource (lib "Integrated_Library_FEDEVEL_APR_2015") (part "ATMEGA16U2-AU"))
    )
    (comp (ref "U3")
      (value "TL1963A-33DCQR")
      (footprint "DCQ (R-PDSO-G6)")
      (description "IC REG LDO 3.3V 1.5A SOT223-6")
      (fields
        (field (name "MANUFACTURER") "Texas Instruments")
        (field (name ".CREATOR") "MM")
        (field (name ".CHECKED PCB") "RF")
        (field (name ".CHECKED SCH") "RF")
      )
      (libsource (lib "Integrated_Library_FEDEVEL_APR_2015") (part "TL1963A-33DCQR"))
    )
    (comp (ref "U4")
      (value "SN74AHC1G09DBVR")
      (footprint "DBV_SOT_23_5")
      (description "IC GATE AND SGL 2INP SOT23-5")
      (fields (field (name "MANUFACTURER") "Texas Instruments") (field (name ".CREATOR") "MM"))
      (libsource (lib "Integrated_Library_FEDEVEL_APR_2015") (part "SN74AHC1G09DBVR"))
    )
    (comp (ref "U5")
      (value "SN74AHC1G09DBVR")
      (footprint "DBV_SOT_23_5")
      (description "IC GATE AND SGL 2INP SOT23-5")
      (fields (field (name "MANUFACTURER") "Texas Instruments") (field (name ".CREATOR") "MM"))
      (libsource (lib "Integrated_Library_FEDEVEL_APR_2015") (part "SN74AHC1G09DBVR"))
    )
    (comp (ref "U6")
      (value "SN74AHC1G09DBVR")
      (footprint "DBV_SOT_23_5")
      (description "IC GATE AND SGL 2INP SOT23-5")
      (fields (field (name "MANUFACTURER") "Texas Instruments") (field (name ".CREATOR") "MM"))
      (libsource (lib "Integrated_Library_FEDEVEL_APR_2015") (part "SN74AHC1G09DBVR"))
    )
    (comp (ref "U7")
      (value "SN74AHC1G09DBVR")
      (footprint "DBV_SOT_23_5")
      (description "IC GATE AND SGL 2INP SOT23-5")
      (fields (field (name "MANUFACTURER") "Texas Instruments") (field (name ".CREATOR") "MM"))
      (libsource (lib "Integrated_Library_FEDEVEL_APR_2015") (part "SN74AHC1G09DBVR"))
    )
    (comp (ref "Y1")
      (value "ABM7-16.000MHZ-D2Y-T")
      (footprint "ABM7_v1_1_BIG")
      (description "CRYSTAL 16MHZ 18PF SMD")
      (fields
        (field (name "MANUFACTURER") "Abracon LLC")
        (field (name ".CREATOR") "MM")
        (field (name ".CHECKED PCB") "RF")
        (field (name ".CHECKED SCH") "RF")
      )
      (libsource (lib "Integrated_Library_FEDEVEL_APR_2015") (part "ABM7-16.000MHZ-D2Y-T"))
    )
    (comp (ref "Y2")
      (value "ABM7-16.000MHZ-D2Y-T")
      (footprint "ABM7_v1_1_BIG")
      (description "CRYSTAL 16MHZ 18PF SMD")
      (fields
        (field (name "MANUFACTURER") "Abracon LLC")
        (field (name ".CREATOR") "MM")
        (field (name ".CHECKED PCB") "RF")
        (field (name ".CHECKED SCH") "RF")
      )
      (libsource (lib "Integrated_Library_FEDEVEL_APR_2015") (part "ABM7-16.000MHZ-D2Y-T"))
    )
    (comp (ref "Z1")
      (value "CG0603MLC-05E")
      (footprint "R0603")
      (description "VARISTOR 0603")
      (fields
        (field (name "MANUFACTURER") "Bourns Inc.")
        (field (name ".CREATOR") "MM")
        (field (name ".CHECKED PCB") "RF")
        (field (name ".CHECKED SCH") "RF")
      )
      (libsource (lib "Integrated_Library_FEDEVEL_APR_2015") (part "CG0603MLC-05E"))
    )
    (comp (ref "Z2")
      (value "CG0603MLC-05E")
      (footprint "R0603")
      (description "VARISTOR 0603")
      (fields
        (field (name "MANUFACTURER") "Bourns Inc.")
        (field (name ".CREATOR") "MM")
        (field (name ".CHECKED PCB") "RF")
        (field (name ".CHECKED SCH") "RF")
      )
      (libsource (lib "Integrated_Library_FEDEVEL_APR_2015") (part "CG0603MLC-05E"))
    )
  )
  (nets
    (net (code "1") (name "+3V3") (class "Default")
      (node (ref "C13") (pin "1") (pinfunction "1_1") (pintype "passive"))
      (node (ref "C16") (pin "1") (pinfunction "1_1") (pintype "passive"))
      (node (ref "J1") (pin "4") (pinfunction "4_4") (pintype "passive"))
      (node (ref "JP4") (pin "3") (pinfunction "3_3") (pintype "passive"))
      (node (ref "R28") (pin "1") (pinfunction "1_1") (pintype "passive"))
      (node (ref "U3") (pin "4") (pinfunction "OUT_4") (pintype "passive"))
      (node (ref "U3") (pin "5") (pinfunction "SENSE_5") (pintype "passive"))
    )
    (net (code "2") (name "+5V") (class "Default")
      (node (ref "C12") (pin "1") (pinfunction "1_1") (pintype "passive"))
      (node (ref "C14") (pin "1") (pinfunction "1_1") (pintype "passive"))
      (node (ref "C2") (pin "1") (pinfunction "1_1") (pintype "passive"))
      (node (ref "C6") (pin "1") (pinfunction "1_1") (pintype "passive"))
      (node (ref "J1") (pin "5") (pinfunction "5_5") (pintype "passive"))
      (node (ref "J8") (pin "1") (pinfunction "1_1") (pintype "passive"))
      (node (ref "JP4") (pin "1") (pinfunction "1_1") (pintype "passive"))
      (node (ref "L1") (pin "2") (pinfunction "2_2") (pintype "passive"))
      (node (ref "R27") (pin "2") (pinfunction "2_2") (pintype "passive"))
      (node (ref "U2") (pin "31") (pinfunction "UVCC_31") (pintype "passive"))
      (node (ref "U3") (pin "1") (pinfunction "~{SHDN}_1") (pintype "passive"))
      (node (ref "U3") (pin "2") (pinfunction "IN_2") (pintype "passive"))
    )
    (net (code "3") (name "+5V{slash}3V3") (class "Default")
      (node (ref "C15") (pin "1") (pinfunction "1_1") (pintype "passive"))
      (node (ref "C17") (pin "1") (pinfunction "1_1") (pintype "passive"))
      (node (ref "C26") (pin "1") (pinfunction "1_1") (pintype "passive"))
      (node (ref "C28") (pin "1") (pinfunction "1_1") (pintype "passive"))
      (node (ref "C29") (pin "1") (pinfunction "1_1") (pintype "passive"))
      (node (ref "C30") (pin "1") (pinfunction "1_1") (pintype "passive"))
      (node (ref "C34") (pin "1") (pinfunction "1_1") (pintype "passive"))
      (node (ref "C8") (pin "1") (pinfunction "1_1") (pintype "passive"))
      (node (ref "D5") (pin "1") (pinfunction "Cathode_1") (pintype "passive"))
      (node (ref "D6") (pin "1") (pinfunction "Cathode_1") (pintype "passive"))
      (node (ref "FB1") (pin "1") (pinfunction "1_1") (pintype "passive"))
      (node (ref "FB2") (pin "1") (pinfunction "1_1") (pintype "passive"))
      (node (ref "FB3") (pin "1") (pinfunction "1_1") (pintype "passive"))
      (node (ref "J1") (pin "2") (pinfunction "2_2") (pintype "passive"))
      (node (ref "J5") (pin "2") (pinfunction "2_2") (pintype "passive"))
      (node (ref "J6") (pin "2") (pinfunction "2_2") (pintype "passive"))
      (node (ref "JP4") (pin "2") (pinfunction "2_2") (pintype "passive"))
      (node (ref "R1") (pin "2") (pinfunction "2_2") (pintype "passive"))
      (node (ref "R14") (pin "2") (pinfunction "2_2") (pintype "passive"))
      (node (ref "R15") (pin "2") (pinfunction "2_2") (pintype "passive"))
      (node (ref "R17") (pin "2") (pinfunction "2_2") (pintype "passive"))
      (node (ref "R18") (pin "2") (pinfunction "2_2") (pintype "passive"))
      (node (ref "R19") (pin "2") (pinfunction "2_2") (pintype "passive"))
      (node (ref "R2") (pin "2") (pinfunction "2_2") (pintype "passive"))
      (node (ref "R20") (pin "2") (pinfunction "2_2") (pintype "passive"))
      (node (ref "R21") (pin "2") (pinfunction "2_2") (pintype "passive"))
      (node (ref "R27") (pin "1") (pinfunction "1_1") (pintype "passive"))
      (node (ref "R28") (pin "2") (pinfunction "2_2") (pintype "passive"))
      (node (ref "R3") (pin "2") (pinfunction "2_2") (pintype "passive"))
      (node (ref "R4") (pin "2") (pinfunction "2_2") (pintype "passive"))
      (node (ref "U4") (pin "5") (pinfunction "VCC_5") (pintype "power_in"))
      (node (ref "U5") (pin "5") (pinfunction "VCC_5") (pintype "power_in"))
      (node (ref "U6") (pin "5") (pinfunction "VCC_5") (pintype "power_in"))
      (node (ref "U7") (pin "5") (pinfunction "VCC_5") (pintype "power_in"))
    )
    (net (code "4") (name "+AREF") (class "Default")
      (node (ref "C21") (pin "1") (pinfunction "1_1") (pintype "passive"))
      (node (ref "C24") (pin "1") (pinfunction "1_1") (pintype "passive"))
      (node (ref "J4") (pin "8") (pinfunction "8_8") (pintype "passive"))
      (node (ref "U1") (pin "21") (pinfunction "AREF_21") (pintype "passive"))
    )
    (net (code "5") (name "/+3V3_16U2_UCAP") (class "Default")
      (node (ref "C7") (pin "2") (pinfunction "2_2") (pintype "passive"))
      (node (ref "R26") (pin "1") (pinfunction "1_1") (pintype "passive"))
      (node (ref "U2") (pin "27") (pinfunction "UCAP_27") (pintype "passive"))
    )
    (net (code "6") (name "/+5V_USB") (class "Default")
      (node (ref "C1") (pin "1") (pinfunction "1_1") (pintype "passive"))
      (node (ref "J7") (pin "1") (pinfunction "P1_1") (pintype "passive"))
      (node (ref "L1") (pin "1") (pinfunction "1_1") (pintype "passive"))
    )
    (net (code "7") (name "/+5V{slash}3V3_16U2") (class "Default")
      (node (ref "FB1") (pin "2") (pinfunction "2_2") (pintype "passive"))
      (node (ref "R26") (pin "2") (pinfunction "2_2") (pintype "passive"))
      (node (ref "U2") (pin "32") (pinfunction "AVCC_32") (pintype "passive"))
      (node (ref "U2") (pin "4") (pinfunction "VCC_4") (pintype "passive"))
    )
    (net (code "8") (name "/+5V{slash}3V3_328P_AVCC") (class "Default")
      (node (ref "C22") (pin "1") (pinfunction "1_1") (pintype "passive"))
      (node (ref "C23") (pin "1") (pinfunction "1_1") (pintype "passive"))
      (node (ref "FB3") (pin "2") (pinfunction "2_2") (pintype "passive"))
      (node (ref "U1") (pin "20") (pinfunction "AVCC_20") (pintype "passive"))
    )
    (net (code "9") (name "/+5V{slash}3V3_328P_VCC") (class "Default")
      (node (ref "C19") (pin "1") (pinfunction "1_1") (pintype "passive"))
      (node (ref "C20") (pin "1") (pinfunction "1_1") (pintype "passive"))
      (node (ref "FB2") (pin "2") (pinfunction "2_2") (pintype "passive"))
      (node (ref "U1") (pin "7") (pinfunction "VCC_7") (pintype "passive"))
    )
    (net (code "10") (name "/16U2PROG_328P_RESETn") (class "Default")
      (node (ref "JP1") (pin "2") (pinfunction "2_2") (pintype "passive"))
      (node (ref "R1") (pin "1") (pinfunction "1_1") (pintype "passive"))
      (node (ref "U2") (pin "13") (pinfunction "~{CTS}_/~{_HWB}_/_T0_/_AIN6_/_INT7_/_PD7_13") (pintype "passive"))
    )
    (net (code "11") (name "/16U2_16MHZ_XTAL1") (class "Default")
      (node (ref "C10") (pin "2") (pinfunction "2_2") (pintype "passive"))
      (node (ref "R9") (pin "1") (pinfunction "1_1") (pintype "passive"))
      (node (ref "U2") (pin "1") (pinfunction "XTAL1_1") (pintype "passive"))
      (node (ref "Y2") (pin "1") (pinfunction "1_1") (pintype "passive"))
    )
    (net (code "12") (name "/16U2_16MHZ_XTAL2") (class "Default")
      (node (ref "C9") (pin "2") (pinfunction "2_2") (pintype "passive"))
      (node (ref "R9") (pin "2") (pinfunction "2_2") (pintype "passive"))
      (node (ref "U2") (pin "2") (pinfunction "XTAL2_/_PC0_2") (pintype "passive"))
      (node (ref "Y2") (pin "2") (pinfunction "2_2") (pintype "passive"))
    )
    (net (code "13") (name "/16U2_BUF_RESETn") (class "Default")
      (node (ref "C31") (pin "1") (pinfunction "1_1") (pintype "passive"))
      (node (ref "R23") (pin "2") (pinfunction "2_2") (pintype "passive"))
      (node (ref "U5") (pin "1") (pinfunction "A_1") (pintype "passive"))
      (node (ref "U5") (pin "2") (pinfunction "B_2") (pintype "passive"))
    )
    (net (code "14") (name "/16U2_HDR_RESETn") (class "Default")
      (node (ref "J6") (pin "5") (pinfunction "5_5") (pintype "passive"))
      (node (ref "JP3") (pin "3") (pinfunction "3_3") (pintype "passive"))
    )
    (net (code "15") (name "/16U2_MISO") (class "Default")
      (node (ref "J6") (pin "1") (pinfunction "1_1") (pintype "passive"))
      (node (ref "U2") (pin "17") (pinfunction "PDO_/_MISO_/_PCINT3_/_PB3_17") (pintype "passive"))
    )
    (net (code "16") (name "/16U2_MOSI") (class "Default")
      (node (ref "J6") (pin "4") (pinfunction "4_4") (pintype "passive"))
      (node (ref "U2") (pin "16") (pinfunction "PDI_/_MOSI_/_PCINT2_/_PB2_16") (pintype "passive"))
    )
    (net (code "17") (name "/16U2_PB4") (class "Default")
      (node (ref "JP2") (pin "1") (pinfunction "1_1") (pintype "passive"))
      (node (ref "JP3") (pin "2") (pinfunction "2_2") (pintype "passive"))
      (node (ref "U2") (pin "18") (pinfunction "T1_/_PCINT4_/_PB4_18") (pintype "passive"))
    )
    (net (code "18") (name "/16U2_PB5") (class "Default")
      (node (ref "JP2") (pin "3") (pinfunction "3_3") (pintype "passive"))
      (node (ref "U2") (pin "19") (pinfunction "PCINT5_/_PB5_19") (pintype "passive"))
    )
    (net (code "19") (name "/16U2_PB6") (class "Default")
      (node (ref "JP2") (pin "2") (pinfunction "2_2") (pintype "passive"))
      (node (ref "U2") (pin "20") (pinfunction "PCINT6_/_PB6_20") (pintype "passive"))
    )
    (net (code "20") (name "/16U2_PB7") (class "Default")
      (node (ref "JP2") (pin "4") (pinfunction "4_4") (pintype "passive"))
      (node (ref "U2") (pin "21") (pinfunction "OC.0A_/_OC.1C_/_PCINT7_/_PB7_21") (pintype "passive"))
    )
    (net (code "21") (name "/16U2_RESETn") (class "Default")
      (node (ref "JP3") (pin "4") (pinfunction "4_4") (pintype "passive"))
      (node (ref "R4") (pin "1") (pinfunction "1_1") (pintype "passive"))
      (node (ref "U2") (pin "24") (pinfunction "PC1_/~{_RESET}_/_DW_24") (pintype "passive"))
      (node (ref "U5") (pin "4") (pinfunction "Y_4") (pintype "passive"))
    )
    (net (code "22") (name "/16U2_RXD") (class "Default")
      (node (ref "R11") (pin "1") (pinfunction "1_1") (pintype "passive"))
      (node (ref "U2") (pin "8") (pinfunction "RXD1_/_AIN1_/_INT2_/_PD2_8") (pintype "passive"))
    )
    (net (code "23") (name "/16U2_RX_LED") (class "Default")
      (node (ref "D4") (pin "1") (pinfunction "cathode_1") (pintype "passive"))
      (node (ref "U2") (pin "10") (pinfunction "AIN3_/_INT5_/_PD4_10") (pintype "passive"))
    )
    (net (code "24") (name "/16U2_SCLK") (class "Default")
      (node (ref "J6") (pin "3") (pinfunction "3_3") (pintype "passive"))
      (node (ref "R5") (pin "2") (pinfunction "2_2") (pintype "passive"))
    )
    (net (code "25") (name "/16U2_SCLK_R") (class "Default")
      (node (ref "R5") (pin "1") (pinfunction "1_1") (pintype "passive"))
      (node (ref "U2") (pin "15") (pinfunction "SCLK_/_PCINT1_/_PB1_15") (pintype "passive"))
    )
    (net (code "26") (name "/16U2_TXD") (class "Default")
      (node (ref "R10") (pin "1") (pinfunction "1_1") (pintype "passive"))
      (node (ref "U2") (pin "9") (pinfunction "TXD1_/_INT3_/_PD3_9") (pintype "passive"))
    )
    (net (code "27") (name "/16U2_TX_LED") (class "Default")
      (node (ref "D3") (pin "1") (pinfunction "cathode_1") (pintype "passive"))
      (node (ref "U2") (pin "11") (pinfunction "XCK_/_AIN4_/_PCINT12_/_PD5_11") (pintype "passive"))
    )
    (net (code "28") (name "/328P_16MHZ_XTAL1") (class "Default")
      (node (ref "C27") (pin "2") (pinfunction "2_2") (pintype "passive"))
      (node (ref "R16") (pin "1") (pinfunction "1_1") (pintype "passive"))
      (node (ref "U1") (pin "9") (pinfunction "PB6_/_PCINT6_/_TOSC1_/_XTAL1_9") (pintype "passive"))
      (node (ref "Y1") (pin "1") (pinfunction "1_1") (pintype "passive"))
    )
    (net (code "29") (name "/328P_16MHZ_XTAL2") (class "Default")
      (node (ref "C25") (pin "2") (pinfunction "2_2") (pintype "passive"))
      (node (ref "R16") (pin "2") (pinfunction "2_2") (pintype "passive"))
      (node (ref "U1") (pin "10") (pinfunction "PB7_/_PCINT7_/_TOSC2_/_XTAL2_10") (pintype "passive"))
      (node (ref "Y1") (pin "2") (pinfunction "2_2") (pintype "passive"))
    )
    (net (code "30") (name "/328P_AUTORESETn") (class "Default")
      (node (ref "C11") (pin "1") (pinfunction "1_1") (pintype "passive"))
      (node (ref "R18") (pin "1") (pinfunction "1_1") (pintype "passive"))
      (node (ref "U6") (pin "1") (pinfunction "A_1") (pintype "passive"))
    )
    (net (code "31") (name "/328P_BUF_RESETn") (class "Default")
      (node (ref "C32") (pin "1") (pinfunction "1_1") (pintype "passive"))
      (node (ref "R24") (pin "2") (pinfunction "2_2") (pintype "passive"))
      (node (ref "U6") (pin "2") (pinfunction "B_2") (pintype "passive"))
    )
    (net (code "32") (name "/328P_RESETn") (class "Default")
      (node (ref "J1") (pin "3") (pinfunction "3_3") (pintype "passive"))
      (node (ref "J5") (pin "5") (pinfunction "5_5") (pintype "passive"))
      (node (ref "JP3") (pin "1") (pinfunction "1_1") (pintype "passive"))
      (node (ref "R14") (pin "1") (pinfunction "1_1") (pintype "passive"))
      (node (ref "U1") (pin "1") (pinfunction "PC6_/_PCINT14_/~{_RESET}_1") (pintype "passive"))
      (node (ref "U6") (pin "4") (pinfunction "Y_4") (pintype "passive"))
    )
    (net (code "33") (name "/AD0") (class "Default")
      (node (ref "J2") (pin "1") (pinfunction "1_1") (pintype "passive"))
      (node (ref "U1") (pin "23") (pinfunction "PCINT8_/_ADC0_/_PC0_23") (pintype "passive"))
    )
    (net (code "34") (name "/AD1") (class "Default")
      (node (ref "J2") (pin "2") (pinfunction "2_2") (pintype "passive"))
      (node (ref "U1") (pin "24") (pinfunction "PCINT9_/_ADC1_/_PC1_24") (pintype "passive"))
    )
    (net (code "35") (name "/AD2") (class "Default")
      (node (ref "J2") (pin "3") (pinfunction "3_3") (pintype "passive"))
      (node (ref "U1") (pin "25") (pinfunction "PCINT10_/_ADC2_/_PC2_25") (pintype "passive"))
    )
    (net (code "36") (name "/AD3") (class "Default")
      (node (ref "J2") (pin "4") (pinfunction "4_4") (pintype "passive"))
      (node (ref "U1") (pin "26") (pinfunction "PCINT11_/_ADC3_/_PC3_26") (pintype "passive"))
    )
    (net (code "37") (name "/AD4{slash}SDA") (class "Default")
      (node (ref "J2") (pin "5") (pinfunction "5_5") (pintype "passive"))
      (node (ref "J4") (pin "9") (pinfunction "9_9") (pintype "passive"))
      (node (ref "U1") (pin "27") (pinfunction "SDA_/_PCINT12_/_ADC4_/_PC4_27") (pintype "passive"))
    )
    (net (code "38") (name "/AD5{slash}SCL") (class "Default")
      (node (ref "J2") (pin "6") (pinfunction "6_6") (pintype "passive"))
      (node (ref "J4") (pin "10") (pinfunction "10_10") (pintype "passive"))
      (node (ref "U1") (pin "28") (pinfunction "SCL_/_PCINT13_/_ADC5_/_PC5_28") (pintype "passive"))
    )
    (net (code "39") (name "/BUTTON_RESETn") (class "Default")
      (node (ref "D6") (pin "2") (pinfunction "Anode_2") (pintype "passive"))
      (node (ref "R20") (pin "1") (pinfunction "1_1") (pintype "passive"))
      (node (ref "R24") (pin "1") (pinfunction "1_1") (pintype "passive"))
      (node (ref "SW1") (pin "1") (pinfunction "1_1") (pintype "passive"))
      (node (ref "SW1") (pin "2") (pinfunction "2_2") (pintype "passive"))
    )
    (net (code "40") (name "/CON_USB_N") (class "Default")
      (node (ref "J7") (pin "2") (pinfunction "P2_2") (pintype "passive"))
      (node (ref "R6") (pin "1") (pinfunction "1_1") (pintype "passive"))
      (node (ref "Z1") (pin "2") (pinfunction "2_2") (pintype "passive"))
    )
    (net (code "41") (name "/CON_USB_P") (class "Default")
      (node (ref "J7") (pin "3") (pinfunction "P3_3") (pintype "passive"))
      (node (ref "R7") (pin "1") (pinfunction "1_1") (pintype "passive"))
      (node (ref "Z2") (pin "2") (pinfunction "2_2") (pintype "passive"))
    )
    (net (code "42") (name "/IO0") (class "Default")
      (node (ref "J3") (pin "1") (pinfunction "1_1") (pintype "passive"))
      (node (ref "R10") (pin "2") (pinfunction "2_2") (pintype "passive"))
      (node (ref "U1") (pin "2") (pinfunction "RXD_/_PCINT16_/_PD0_2") (pintype "passive"))
    )
    (net (code "43") (name "/IO1") (class "Default")
      (node (ref "J3") (pin "2") (pinfunction "2_2") (pintype "passive"))
      (node (ref "R11") (pin "2") (pinfunction "2_2") (pintype "passive"))
      (node (ref "U1") (pin "3") (pinfunction "TXD_/_PCINT17_/_PD1_3") (pintype "passive"))
    )
    (net (code "44") (name "/IO2") (class "Default")
      (node (ref "J3") (pin "3") (pinfunction "3_3") (pintype "passive"))
      (node (ref "U1") (pin "4") (pinfunction "INT0_/_PCINT18_/_PD2_4") (pintype "passive"))
    )
    (net (code "45") (name "/IO3") (class "Default")
      (node (ref "J3") (pin "4") (pinfunction "4_4") (pintype "passive"))
      (node (ref "U1") (pin "5") (pinfunction "OC2B_/_INT1_/_PCINT19_/_PD3_5") (pintype "passive"))
    )
    (net (code "46") (name "/IO4") (class "Default")
      (node (ref "J3") (pin "5") (pinfunction "5_5") (pintype "passive"))
      (node (ref "U1") (pin "6") (pinfunction "XCK_/_T0_/_PCINT20_/_PD4_6") (pintype "passive"))
    )
    (net (code "47") (name "/IO5") (class "Default")
      (node (ref "J3") (pin "6") (pinfunction "6_6") (pintype "passive"))
      (node (ref "U1") (pin "11") (pinfunction "OC0B_/_T1_/_PCINT21_/_PD5_11") (pintype "passive"))
    )
    (net (code "48") (name "/IO6") (class "Default")
      (node (ref "J3") (pin "7") (pinfunction "7_7") (pintype "passive"))
      (node (ref "U1") (pin "12") (pinfunction "OC0A_/_AIN0_/_PCINT22_/_PD6_12") (pintype "passive"))
    )
    (net (code "49") (name "/IO7") (class "Default")
      (node (ref "J3") (pin "8") (pinfunction "8_8") (pintype "passive"))
      (node (ref "U1") (pin "13") (pinfunction "AIN1_/_PCINT23_/_PD7_13") (pintype "passive"))
    )
    (net (code "50") (name "/IO8") (class "Default")
      (node (ref "J4") (pin "1") (pinfunction "1_1") (pintype "passive"))
      (node (ref "R22") (pin "1") (pinfunction "1_1") (pintype "passive"))
      (node (ref "U1") (pin "14") (pinfunction "CLKO_/_ICP1_/_PCINT0_/_PB0_14") (pintype "passive"))
    )
    (net (code "51") (name "/IO9") (class "Default")
      (node (ref "J4") (pin "2") (pinfunction "2_2") (pintype "passive"))
      (node (ref "U1") (pin "15") (pinfunction "OC1A_/_PCINT1_/_PB1_15") (pintype "passive"))
    )
    (net (code "52") (name "/MISO") (class "Default")
      (node (ref "J4") (pin "5") (pinfunction "5_5") (pintype "passive"))
      (node (ref "J5") (pin "1") (pinfunction "1_1") (pintype "passive"))
      (node (ref "U1") (pin "18") (pinfunction "MISO_/_PCINT4_/_PB4_18") (pintype "passive"))
    )
    (net (code "53") (name "/MOSI") (class "Default")
      (node (ref "J4") (pin "4") (pinfunction "4_4") (pintype "passive"))
      (node (ref "J5") (pin "4") (pinfunction "4_4") (pintype "passive"))
      (node (ref "U1") (pin "17") (pinfunction "MOSI_/_OC2A_/_PCINT3_/_PB3_17") (pintype "passive"))
    )
    (net (code "54") (name "/SCK") (class "Default")
      (node (ref "J4") (pin "6") (pinfunction "6_6") (pintype "passive"))
      (node (ref "J5") (pin "3") (pinfunction "3_3") (pintype "passive"))
      (node (ref "R13") (pin "2") (pinfunction "2_2") (pintype "passive"))
      (node (ref "U4") (pin "1") (pinfunction "A_1") (pintype "passive"))
      (node (ref "U4") (pin "2") (pinfunction "B_2") (pintype "passive"))
    )
    (net (code "55") (name "/SCK_R") (class "Default")
      (node (ref "R13") (pin "1") (pinfunction "1_1") (pintype "passive"))
      (node (ref "U1") (pin "19") (pinfunction "SCK_/_PCINT5_/_PB5_19") (pintype "passive"))
    )
    (net (code "56") (name "/SS") (class "Default")
      (node (ref "J4") (pin "3") (pinfunction "3_3") (pintype "passive"))
      (node (ref "U1") (pin "16") (pinfunction "~{SS}_/_OC1B_/_PCINT2_/_PB2_16") (pintype "passive"))
    )
    (net (code "57") (name "/USB_N") (class "Default")
      (node (ref "R6") (pin "2") (pinfunction "2_2") (pintype "passive"))
      (node (ref "U2") (pin "30") (pinfunction "D-_30") (pintype "passive"))
    )
    (net (code "58") (name "/USB_P") (class "Default")
      (node (ref "R7") (pin "2") (pinfunction "2_2") (pintype "passive"))
      (node (ref "U2") (pin "29") (pinfunction "D+_29") (pintype "passive"))
    )
    (net (code "59") (name "/USER_BUTTON") (class "Default")
      (node (ref "R21") (pin "1") (pinfunction "1_1") (pintype "passive"))
      (node (ref "R25") (pin "1") (pinfunction "1_1") (pintype "passive"))
      (node (ref "SW2") (pin "1") (pinfunction "1_1") (pintype "passive"))
      (node (ref "SW2") (pin "2") (pinfunction "2_2") (pintype "passive"))
    )
    (net (code "60") (name "/USER_BUTTON_BUF") (class "Default")
      (node (ref "C33") (pin "1") (pinfunction "1_1") (pintype "passive"))
      (node (ref "R25") (pin "2") (pinfunction "2_2") (pintype "passive"))
      (node (ref "U7") (pin "1") (pinfunction "A_1") (pintype "passive"))
      (node (ref "U7") (pin "2") (pinfunction "B_2") (pintype "passive"))
    )
    (net (code "61") (name "GND") (class "Default")
      (node (ref "C1") (pin "2") (pinfunction "2_2") (pintype "passive"))
      (node (ref "C10") (pin "1") (pinfunction "1_1") (pintype "passive"))
      (node (ref "C12") (pin "2") (pinfunction "2_2") (pintype "passive"))
      (node (ref "C13") (pin "2") (pinfunction "2_2") (pintype "passive"))
      (node (ref "C14") (pin "2") (pinfunction "2_2") (pintype "passive"))
      (node (ref "C15") (pin "2") (pinfunction "2_2") (pintype "passive"))
      (node (ref "C16") (pin "2") (pinfunction "2_2") (pintype "passive"))
      (node (ref "C17") (pin "2") (pinfunction "2_2") (pintype "passive"))
      (node (ref "C19") (pin "2") (pinfunction "2_2") (pintype "passive"))
      (node (ref "C2") (pin "2") (pinfunction "2_2") (pintype "passive"))
      (node (ref "C20") (pin "2") (pinfunction "2_2") (pintype "passive"))
      (node (ref "C21") (pin "2") (pinfunction "2_2") (pintype "passive"))
      (node (ref "C22") (pin "2") (pinfunction "2_2") (pintype "passive"))
      (node (ref "C23") (pin "2") (pinfunction "2_2") (pintype "passive"))
      (node (ref "C24") (pin "2") (pinfunction "2_2") (pintype "passive"))
      (node (ref "C25") (pin "1") (pinfunction "1_1") (pintype "passive"))
      (node (ref "C26") (pin "2") (pinfunction "2_2") (pintype "passive"))
      (node (ref "C27") (pin "1") (pinfunction "1_1") (pintype "passive"))
      (node (ref "C28") (pin "2") (pinfunction "2_2") (pintype "passive"))
      (node (ref "C29") (pin "2") (pinfunction "2_2") (pintype "passive"))
      (node (ref "C30") (pin "2") (pinfunction "2_2") (pintype "passive"))
      (node (ref "C31") (pin "2") (pinfunction "2_2") (pintype "passive"))
      (node (ref "C32") (pin "2") (pinfunction "2_2") (pintype "passive"))
      (node (ref "C33") (pin "2") (pinfunction "2_2") (pintype "passive"))
      (node (ref "C34") (pin "2") (pinfunction "2_2") (pintype "passive"))
      (node (ref "C6") (pin "2") (pinfunction "2_2") (pintype "passive"))
      (node (ref "C7") (pin "1") (pinfunction "1_1") (pintype "passive"))
      (node (ref "C8") (pin "2") (pinfunction "2_2") (pintype "passive"))
      (node (ref "C9") (pin "1") (pinfunction "1_1") (pintype "passive"))
      (node (ref "D1") (pin "1") (pinfunction "cathode_1") (pintype "passive"))
      (node (ref "J1") (pin "6") (pinfunction "6_6") (pintype "passive"))
      (node (ref "J1") (pin "7") (pinfunction "7_7") (pintype "passive"))
      (node (ref "J4") (pin "7") (pinfunction "7_7") (pintype "passive"))
      (node (ref "J5") (pin "6") (pinfunction "6_6") (pintype "passive"))
      (node (ref "J6") (pin "6") (pinfunction "6_6") (pintype "passive"))
      (node (ref "J7") (pin "10") (pinfunction "10_10") (pintype "passive"))
      (node (ref "J7") (pin "11") (pinfunction "11_11") (pintype "passive"))
      (node (ref "J7") (pin "5") (pinfunction "P5_5") (pintype "passive"))
      (node (ref "J7") (pin "6") (pinfunction "6_6") (pintype "passive"))
      (node (ref "J7") (pin "7") (pinfunction "7_7") (pintype "passive"))
      (node (ref "J7") (pin "8") (pinfunction "8_8") (pintype "passive"))
      (node (ref "J7") (pin "9") (pinfunction "9_9") (pintype "passive"))
      (node (ref "J9") (pin "1") (pinfunction "1_1") (pintype "passive"))
      (node (ref "MH1") (pin "1") (pinfunction "1_1") (pintype "passive"))
      (node (ref "MH2") (pin "1") (pinfunction "1_1") (pintype "passive"))
      (node (ref "MH3") (pin "1") (pinfunction "1_1") (pintype "passive"))
      (node (ref "R12") (pin "2") (pinfunction "2_2") (pintype "passive"))
      (node (ref "R8") (pin "2") (pinfunction "2_2") (pintype "passive"))
      (node (ref "SW1") (pin "3") (pinfunction "MECH1_3") (pintype "passive"))
      (node (ref "SW1") (pin "4") (pinfunction "MECH2_4") (pintype "passive"))
      (node (ref "SW2") (pin "3") (pinfunction "MECH1_3") (pintype "passive"))
      (node (ref "SW2") (pin "4") (pinfunction "MECH2_4") (pintype "passive"))
      (node (ref "U1") (pin "22") (pinfunction "GND_2_22") (pintype "passive"))
      (node (ref "U1") (pin "8") (pinfunction "GND_1_8") (pintype "passive"))
      (node (ref "U2") (pin "28") (pinfunction "UGND_28") (pintype "passive"))
      (node (ref "U2") (pin "3") (pinfunction "GND_3") (pintype "passive"))
      (node (ref "U3") (pin "3") (pinfunction "GND_3") (pintype "passive"))
      (node (ref "U3") (pin "6") (pinfunction "EPAD_6") (pintype "passive"))
      (node (ref "U4") (pin "3") (pinfunction "GND_3") (pintype "power_in"))
      (node (ref "U5") (pin "3") (pinfunction "GND_3") (pintype "power_in"))
      (node (ref "U6") (pin "3") (pinfunction "GND_3") (pintype "power_in"))
      (node (ref "U7") (pin "3") (pinfunction "GND_3") (pintype "power_in"))
      (node (ref "Z1") (pin "1") (pinfunction "1_1") (pintype "passive"))
      (node (ref "Z2") (pin "1") (pinfunction "1_1") (pintype "passive"))
    )
    (net (code "62") (name "Net-(C11-Pad2)") (class "Default")
      (node (ref "C11") (pin "2") (pinfunction "2_2") (pintype "passive"))
      (node (ref "JP1") (pin "1") (pinfunction "1_1") (pintype "passive"))
    )
    (net (code "63") (name "Net-(D1-ANODE)") (class "Default")
      (node (ref "D1") (pin "2") (pinfunction "ANODE_2") (pintype "passive"))
      (node (ref "R17") (pin "1") (pinfunction "1_1") (pintype "passive"))
    )
    (net (code "64") (name "Net-(D2-ANODE)") (class "Default")
      (node (ref "D2") (pin "2") (pinfunction "ANODE_2") (pintype "passive"))
      (node (ref "R15") (pin "1") (pinfunction "1_1") (pintype "passive"))
    )
    (net (code "65") (name "Net-(D2-cathode)") (class "Default")
      (node (ref "D2") (pin "1") (pinfunction "cathode_1") (pintype "passive"))
      (node (ref "U4") (pin "4") (pinfunction "Y_4") (pintype "passive"))
    )
    (net (code "66") (name "Net-(D3-ANODE)") (class "Default")
      (node (ref "D3") (pin "2") (pinfunction "ANODE_2") (pintype "passive"))
      (node (ref "R2") (pin "1") (pinfunction "1_1") (pintype "passive"))
    )
    (net (code "67") (name "Net-(D4-ANODE)") (class "Default")
      (node (ref "D4") (pin "2") (pinfunction "ANODE_2") (pintype "passive"))
      (node (ref "R3") (pin "1") (pinfunction "1_1") (pintype "passive"))
    )
    (net (code "68") (name "Net-(D5-Anode)") (class "Default")
      (node (ref "D5") (pin "2") (pinfunction "Anode_2") (pintype "passive"))
      (node (ref "R19") (pin "1") (pinfunction "1_1") (pintype "passive"))
      (node (ref "R23") (pin "1") (pinfunction "1_1") (pintype "passive"))
    )
    (net (code "69") (name "Net-(J7-P4)") (class "Default")
      (node (ref "J7") (pin "4") (pinfunction "P4_4") (pintype "passive"))
      (node (ref "R8") (pin "1") (pinfunction "1_1") (pintype "passive"))
    )
    (net (code "70") (name "Net-(JP1-Pad3)") (class "Default")
      (node (ref "JP1") (pin "3") (pinfunction "3_3") (pintype "passive"))
      (node (ref "R12") (pin "1") (pinfunction "1_1") (pintype "passive"))
    )
    (net (code "71") (name "Net-(U7-Y)") (class "Default")
      (node (ref "R22") (pin "2") (pinfunction "2_2") (pintype "passive"))
      (node (ref "U7") (pin "4") (pinfunction "Y_4") (pintype "passive"))
    )
    (net (code "72") (name "unconnected-(J1-Pad1)") (class "Default")
      (node (ref "J1") (pin "1") (pinfunction "1_1") (pintype "passive+no_connect"))
    )
    (net (code "73") (name "unconnected-(J1-Pad8)") (class "Default")
      (node (ref "J1") (pin "8") (pinfunction "8_8") (pintype "passive+no_connect"))
    )
    (net (code "74") (name "unconnected-(MH4-Pad1)") (class "Default")
      (node (ref "MH4") (pin "1") (pinfunction "1_1") (pintype "passive+no_connect"))
    )
    (net (code "75") (name "unconnected-(U2-AIN0_{slash}_INT1_{slash}_PD1-Pad7)") (class "Default")
      (node (ref "U2") (pin "7") (pinfunction "AIN0_/_INT1_/_PD1_7") (pintype "passive+no_connect"))
    )
    (net (code "76") (name "unconnected-(U2-AIN2_{slash}_PCINT11_{slash}_PC2-Pad5)") (class "Default")
      (node (ref "U2") (pin "5") (pinfunction "AIN2_/_PCINT11_/_PC2_5") (pintype "passive+no_connect"))
    )
    (net (code "77") (name "unconnected-(U2-CLKO_{slash}_ICP1_{slash}_INT4_{slash}_PC7-Pad22)") (class "Default")
      (node (ref "U2") (pin "22") (pinfunction "CLKO_/_ICP1_/_INT4_/_PC7_22") (pintype "passive+no_connect"))
    )
    (net (code "78") (name "unconnected-(U2-OC.0B_{slash}_INT0_{slash}_PD0-Pad6)") (class "Default")
      (node (ref "U2") (pin "6") (pinfunction "OC.0B_/_INT0_/_PD0_6") (pintype "passive+no_connect"))
    )
    (net (code "79") (name "unconnected-(U2-OC.1A_{slash}_PCINT8_{slash}_PC6-Pad23)") (class "Default")
      (node (ref "U2") (pin "23") (pinfunction "OC.1A_/_PCINT8_/_PC6_23") (pintype "passive+no_connect"))
    )
    (net (code "80") (name "unconnected-(U2-OC.1B_{slash}_PCINT9_{slash}_PC5-Pad25)") (class "Default")
      (node (ref "U2") (pin "25") (pinfunction "OC.1B_/_PCINT9_/_PC5_25") (pintype "passive+no_connect"))
    )
    (net (code "81") (name "unconnected-(U2-PCINT10_{slash}_PC4-Pad26)") (class "Default")
      (node (ref "U2") (pin "26") (pinfunction "PCINT10_/_PC4_26") (pintype "passive+no_connect"))
    )
    (net (code "82") (name "unconnected-(U2-~{RTS}_{slash}_AIN5_{slash}_INT6_{slash}_PD6-Pad12)") (class "Default")
      (node (ref "U2") (pin "12") (pinfunction "~{RTS}_/_AIN5_/_INT6_/_PD6_12") (pintype "passive"))
    )
    (net (code "83") (name "unconnected-(U2-~{SS}_{slash}_PCINT0_{slash}_PB0-Pad14)") (class "Default")
      (node (ref "U2") (pin "14") (pinfunction "~{SS}_/_PCINT0_/_PB0_14") (pintype "passive+no_connect"))
    )
  )
)
